# CONNECTORs.net
KiCad netlist of a schematic drawn in Altium Designer
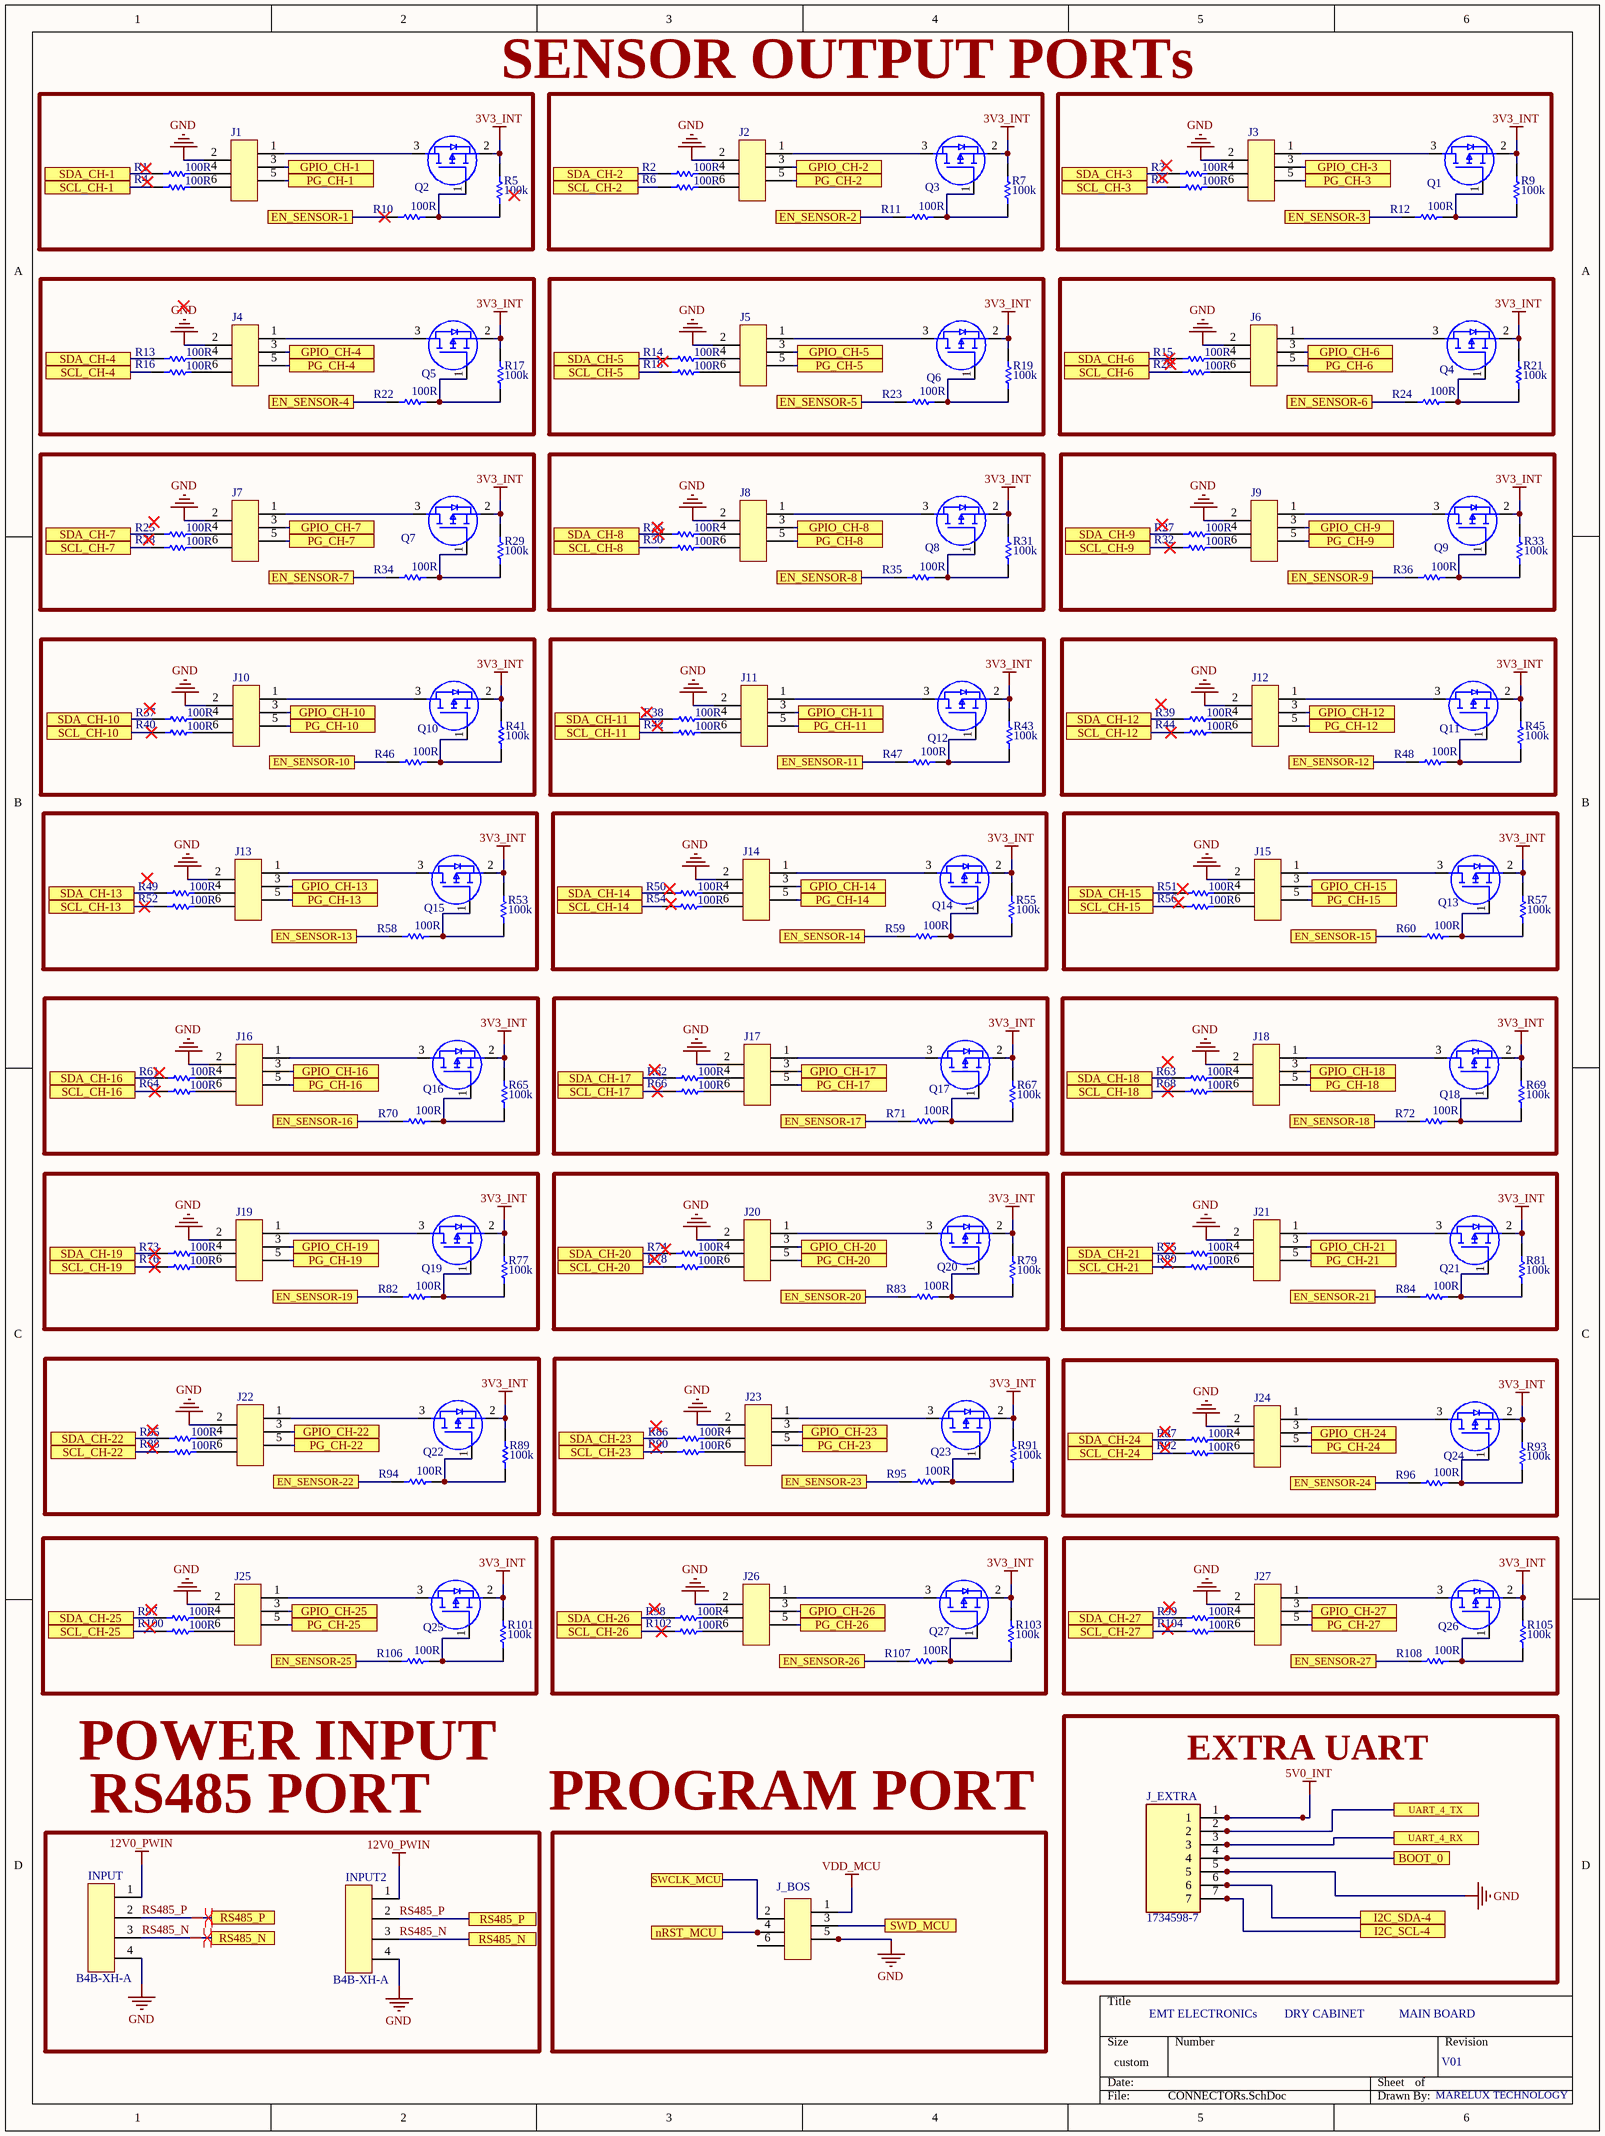
[diagram p0: CONNECTORs.SchDoc]

(export (version "E")
  (design (tool "Eeschema 10.0.6"))
  (components
    (comp (ref "INPUT")
      (value "B4B-XH-A")
      (footprint "B4B-XH-A")
      (description "CONN HEADER VERT 4POS 2.5MM")
      (fields (field (name "MANUFACTURER") "JST"))
      (libsource (lib "MareLux24Lib") (part "B4B-XH-A"))
    )
    (comp (ref "INPUT2")
      (value "B4B-XH-A")
      (footprint "B4B-XH-A")
      (description "CONN HEADER VERT 4POS 2.5MM")
      (fields (field (name "MANUFACTURER") "JST"))
      (libsource (lib "MareLux24Lib") (part "B4B-XH-A"))
    )
    (comp (ref "J1")
      (value "009159006651906")
      (footprint "009159006651906")
      (description "CONN EDGE DUAL FMALE 6POS 0.024")
      (fields (field (name "MANUFACTURER") "KYOCERA AVX"))
      (libsource (lib "MareLux24Lib") (part "009159006651906"))
    )
    (comp (ref "J2")
      (value "009159006651906")
      (footprint "009159006651906")
      (description "CONN EDGE DUAL FMALE 6POS 0.024")
      (fields (field (name "MANUFACTURER") "KYOCERA AVX"))
      (libsource (lib "MareLux24Lib") (part "009159006651906"))
    )
    (comp (ref "J3")
      (value "009159006651906")
      (footprint "009159006651906")
      (description "CONN EDGE DUAL FMALE 6POS 0.024")
      (fields (field (name "MANUFACTURER") "KYOCERA AVX"))
      (libsource (lib "MareLux24Lib") (part "009159006651906"))
    )
    (comp (ref "J4")
      (value "009159006651906")
      (footprint "009159006651906")
      (description "CONN EDGE DUAL FMALE 6POS 0.024")
      (fields (field (name "MANUFACTURER") "KYOCERA AVX"))
      (libsource (lib "MareLux24Lib") (part "009159006651906"))
    )
    (comp (ref "J5")
      (value "009159006651906")
      (footprint "009159006651906")
      (description "CONN EDGE DUAL FMALE 6POS 0.024")
      (fields (field (name "MANUFACTURER") "KYOCERA AVX"))
      (libsource (lib "MareLux24Lib") (part "009159006651906"))
    )
    (comp (ref "J6")
      (value "009159006651906")
      (footprint "009159006651906")
      (description "CONN EDGE DUAL FMALE 6POS 0.024")
      (fields (field (name "MANUFACTURER") "KYOCERA AVX"))
      (libsource (lib "MareLux24Lib") (part "009159006651906"))
    )
    (comp (ref "J7")
      (value "009159006651906")
      (footprint "009159006651906")
      (description "CONN EDGE DUAL FMALE 6POS 0.024")
      (fields (field (name "MANUFACTURER") "KYOCERA AVX"))
      (libsource (lib "MareLux24Lib") (part "009159006651906"))
    )
    (comp (ref "J8")
      (value "009159006651906")
      (footprint "009159006651906")
      (description "CONN EDGE DUAL FMALE 6POS 0.024")
      (fields (field (name "MANUFACTURER") "KYOCERA AVX"))
      (libsource (lib "MareLux24Lib") (part "009159006651906"))
    )
    (comp (ref "J9")
      (value "009159006651906")
      (footprint "009159006651906")
      (description "CONN EDGE DUAL FMALE 6POS 0.024")
      (fields (field (name "MANUFACTURER") "KYOCERA AVX"))
      (libsource (lib "MareLux24Lib") (part "009159006651906"))
    )
    (comp (ref "J10")
      (value "009159006651906")
      (footprint "009159006651906")
      (description "CONN EDGE DUAL FMALE 6POS 0.024")
      (fields (field (name "MANUFACTURER") "KYOCERA AVX"))
      (libsource (lib "MareLux24Lib") (part "009159006651906"))
    )
    (comp (ref "J11")
      (value "009159006651906")
      (footprint "009159006651906")
      (description "CONN EDGE DUAL FMALE 6POS 0.024")
      (fields (field (name "MANUFACTURER") "KYOCERA AVX"))
      (libsource (lib "MareLux24Lib") (part "009159006651906"))
    )
    (comp (ref "J12")
      (value "009159006651906")
      (footprint "009159006651906")
      (description "CONN EDGE DUAL FMALE 6POS 0.024")
      (fields (field (name "MANUFACTURER") "KYOCERA AVX"))
      (libsource (lib "MareLux24Lib") (part "009159006651906"))
    )
    (comp (ref "J13")
      (value "009159006651906")
      (footprint "009159006651906")
      (description "CONN EDGE DUAL FMALE 6POS 0.024")
      (fields (field (name "MANUFACTURER") "KYOCERA AVX"))
      (libsource (lib "MareLux24Lib") (part "009159006651906"))
    )
    (comp (ref "J14")
      (value "009159006651906")
      (footprint "009159006651906")
      (description "CONN EDGE DUAL FMALE 6POS 0.024")
      (fields (field (name "MANUFACTURER") "KYOCERA AVX"))
      (libsource (lib "MareLux24Lib") (part "009159006651906"))
    )
    (comp (ref "J15")
      (value "009159006651906")
      (footprint "009159006651906")
      (description "CONN EDGE DUAL FMALE 6POS 0.024")
      (fields (field (name "MANUFACTURER") "KYOCERA AVX"))
      (libsource (lib "MareLux24Lib") (part "009159006651906"))
    )
    (comp (ref "J16")
      (value "009159006651906")
      (footprint "009159006651906")
      (description "CONN EDGE DUAL FMALE 6POS 0.024")
      (fields (field (name "MANUFACTURER") "KYOCERA AVX"))
      (libsource (lib "MareLux24Lib") (part "009159006651906"))
    )
    (comp (ref "J17")
      (value "009159006651906")
      (footprint "009159006651906")
      (description "CONN EDGE DUAL FMALE 6POS 0.024")
      (fields (field (name "MANUFACTURER") "KYOCERA AVX"))
      (libsource (lib "MareLux24Lib") (part "009159006651906"))
    )
    (comp (ref "J18")
      (value "009159006651906")
      (footprint "009159006651906")
      (description "CONN EDGE DUAL FMALE 6POS 0.024")
      (fields (field (name "MANUFACTURER") "KYOCERA AVX"))
      (libsource (lib "MareLux24Lib") (part "009159006651906"))
    )
    (comp (ref "J19")
      (value "009159006651906")
      (footprint "009159006651906")
      (description "CONN EDGE DUAL FMALE 6POS 0.024")
      (fields (field (name "MANUFACTURER") "KYOCERA AVX"))
      (libsource (lib "MareLux24Lib") (part "009159006651906"))
    )
    (comp (ref "J20")
      (value "009159006651906")
      (footprint "009159006651906")
      (description "CONN EDGE DUAL FMALE 6POS 0.024")
      (fields (field (name "MANUFACTURER") "KYOCERA AVX"))
      (libsource (lib "MareLux24Lib") (part "009159006651906"))
    )
    (comp (ref "J21")
      (value "009159006651906")
      (footprint "009159006651906")
      (description "CONN EDGE DUAL FMALE 6POS 0.024")
      (fields (field (name "MANUFACTURER") "KYOCERA AVX"))
      (libsource (lib "MareLux24Lib") (part "009159006651906"))
    )
    (comp (ref "J22")
      (value "009159006651906")
      (footprint "009159006651906")
      (description "CONN EDGE DUAL FMALE 6POS 0.024")
      (fields (field (name "MANUFACTURER") "KYOCERA AVX"))
      (libsource (lib "MareLux24Lib") (part "009159006651906"))
    )
    (comp (ref "J23")
      (value "009159006651906")
      (footprint "009159006651906")
      (description "CONN EDGE DUAL FMALE 6POS 0.024")
      (fields (field (name "MANUFACTURER") "KYOCERA AVX"))
      (libsource (lib "MareLux24Lib") (part "009159006651906"))
    )
    (comp (ref "J24")
      (value "009159006651906")
      (footprint "009159006651906")
      (description "CONN EDGE DUAL FMALE 6POS 0.024")
      (fields (field (name "MANUFACTURER") "KYOCERA AVX"))
      (libsource (lib "MareLux24Lib") (part "009159006651906"))
    )
    (comp (ref "J25")
      (value "009159006651906")
      (footprint "009159006651906")
      (description "CONN EDGE DUAL FMALE 6POS 0.024")
      (fields (field (name "MANUFACTURER") "KYOCERA AVX"))
      (libsource (lib "MareLux24Lib") (part "009159006651906"))
    )
    (comp (ref "J26")
      (value "009159006651906")
      (footprint "009159006651906")
      (description "CONN EDGE DUAL FMALE 6POS 0.024")
      (fields (field (name "MANUFACTURER") "KYOCERA AVX"))
      (libsource (lib "MareLux24Lib") (part "009159006651906"))
    )
    (comp (ref "J27")
      (value "009159006651906")
      (footprint "009159006651906")
      (description "CONN EDGE DUAL FMALE 6POS 0.024")
      (fields (field (name "MANUFACTURER") "KYOCERA AVX"))
      (libsource (lib "MareLux24Lib") (part "009159006651906"))
    )
    (comp (ref "J_BOS")
      (value "009159006651906")
      (footprint "009159006651906")
      (description "CONN EDGE DUAL FMALE 6POS 0.024")
      (fields (field (name "MANUFACTURER") "KYOCERA AVX"))
      (libsource (lib "MareLux24Lib") (part "009159006651906"))
    )
    (comp (ref "J_EXTRA")
      (value "1734598-7")
      (footprint "TE_1734598-7")
      (description "Connector Header Through Hole 7 position 0.049 (1.25mm)")
      (fields (field (name "DIGI-KEY_PART_NUMBER") "A99919-ND") (field (name "MF") "TE Connectivity"))
      (libsource (lib "1734598-7") (part "1734598-7"))
    )
    (comp (ref "Q1")
      (value "GSF3407")
      (footprint "SOT-23")
      (description "P-Channel 30 V 4.1A (Ta) 1.2W (Ta) Surface Mount SOT-23")
      (fields (field (name "VOLTAGE") "30 V") (field (name "POWER") "1200 mW"))
      (libsource (lib "MareLux24Lib") (part "GSF3407"))
    )
    (comp (ref "Q2")
      (value "GSF3407")
      (footprint "SOT-23")
      (description "P-Channel 30 V 4.1A (Ta) 1.2W (Ta) Surface Mount SOT-23")
      (fields (field (name "VOLTAGE") "30 V") (field (name "POWER") "1200 mW"))
      (libsource (lib "MareLux24Lib") (part "GSF3407"))
    )
    (comp (ref "Q3")
      (value "GSF3407")
      (footprint "SOT-23")
      (description "P-Channel 30 V 4.1A (Ta) 1.2W (Ta) Surface Mount SOT-23")
      (fields (field (name "VOLTAGE") "30 V") (field (name "POWER") "1200 mW"))
      (libsource (lib "MareLux24Lib") (part "GSF3407"))
    )
    (comp (ref "Q4")
      (value "GSF3407")
      (footprint "SOT-23")
      (description "P-Channel 30 V 4.1A (Ta) 1.2W (Ta) Surface Mount SOT-23")
      (fields (field (name "VOLTAGE") "30 V") (field (name "POWER") "1200 mW"))
      (libsource (lib "MareLux24Lib") (part "GSF3407"))
    )
    (comp (ref "Q5")
      (value "GSF3407")
      (footprint "SOT-23")
      (description "P-Channel 30 V 4.1A (Ta) 1.2W (Ta) Surface Mount SOT-23")
      (fields (field (name "VOLTAGE") "30 V") (field (name "POWER") "1200 mW"))
      (libsource (lib "MareLux24Lib") (part "GSF3407"))
    )
    (comp (ref "Q6")
      (value "GSF3407")
      (footprint "SOT-23")
      (description "P-Channel 30 V 4.1A (Ta) 1.2W (Ta) Surface Mount SOT-23")
      (fields (field (name "VOLTAGE") "30 V") (field (name "POWER") "1200 mW"))
      (libsource (lib "MareLux24Lib") (part "GSF3407"))
    )
    (comp (ref "Q7")
      (value "GSF3407")
      (footprint "SOT-23")
      (description "P-Channel 30 V 4.1A (Ta) 1.2W (Ta) Surface Mount SOT-23")
      (fields (field (name "VOLTAGE") "30 V") (field (name "POWER") "1200 mW"))
      (libsource (lib "MareLux24Lib") (part "GSF3407"))
    )
    (comp (ref "Q8")
      (value "GSF3407")
      (footprint "SOT-23")
      (description "P-Channel 30 V 4.1A (Ta) 1.2W (Ta) Surface Mount SOT-23")
      (fields (field (name "VOLTAGE") "30 V") (field (name "POWER") "1200 mW"))
      (libsource (lib "MareLux24Lib") (part "GSF3407"))
    )
    (comp (ref "Q9")
      (value "GSF3407")
      (footprint "SOT-23")
      (description "P-Channel 30 V 4.1A (Ta) 1.2W (Ta) Surface Mount SOT-23")
      (fields (field (name "VOLTAGE") "30 V") (field (name "POWER") "1200 mW"))
      (libsource (lib "MareLux24Lib") (part "GSF3407"))
    )
    (comp (ref "Q10")
      (value "GSF3407")
      (footprint "SOT-23")
      (description "P-Channel 30 V 4.1A (Ta) 1.2W (Ta) Surface Mount SOT-23")
      (fields (field (name "VOLTAGE") "30 V") (field (name "POWER") "1200 mW"))
      (libsource (lib "MareLux24Lib") (part "GSF3407"))
    )
    (comp (ref "Q11")
      (value "GSF3407")
      (footprint "SOT-23")
      (description "P-Channel 30 V 4.1A (Ta) 1.2W (Ta) Surface Mount SOT-23")
      (fields (field (name "VOLTAGE") "30 V") (field (name "POWER") "1200 mW"))
      (libsource (lib "MareLux24Lib") (part "GSF3407"))
    )
    (comp (ref "Q12")
      (value "GSF3407")
      (footprint "SOT-23")
      (description "P-Channel 30 V 4.1A (Ta) 1.2W (Ta) Surface Mount SOT-23")
      (fields (field (name "VOLTAGE") "30 V") (field (name "POWER") "1200 mW"))
      (libsource (lib "MareLux24Lib") (part "GSF3407"))
    )
    (comp (ref "Q13")
      (value "GSF3407")
      (footprint "SOT-23")
      (description "P-Channel 30 V 4.1A (Ta) 1.2W (Ta) Surface Mount SOT-23")
      (fields (field (name "VOLTAGE") "30 V") (field (name "POWER") "1200 mW"))
      (libsource (lib "MareLux24Lib") (part "GSF3407"))
    )
    (comp (ref "Q14")
      (value "GSF3407")
      (footprint "SOT-23")
      (description "P-Channel 30 V 4.1A (Ta) 1.2W (Ta) Surface Mount SOT-23")
      (fields (field (name "VOLTAGE") "30 V") (field (name "POWER") "1200 mW"))
      (libsource (lib "MareLux24Lib") (part "GSF3407"))
    )
    (comp (ref "Q15")
      (value "GSF3407")
      (footprint "SOT-23")
      (description "P-Channel 30 V 4.1A (Ta) 1.2W (Ta) Surface Mount SOT-23")
      (fields (field (name "VOLTAGE") "30 V") (field (name "POWER") "1200 mW"))
      (libsource (lib "MareLux24Lib") (part "GSF3407"))
    )
    (comp (ref "Q16")
      (value "GSF3407")
      (footprint "SOT-23")
      (description "P-Channel 30 V 4.1A (Ta) 1.2W (Ta) Surface Mount SOT-23")
      (fields (field (name "VOLTAGE") "30 V") (field (name "POWER") "1200 mW"))
      (libsource (lib "MareLux24Lib") (part "GSF3407"))
    )
    (comp (ref "Q17")
      (value "GSF3407")
      (footprint "SOT-23")
      (description "P-Channel 30 V 4.1A (Ta) 1.2W (Ta) Surface Mount SOT-23")
      (fields (field (name "VOLTAGE") "30 V") (field (name "POWER") "1200 mW"))
      (libsource (lib "MareLux24Lib") (part "GSF3407"))
    )
    (comp (ref "Q18")
      (value "GSF3407")
      (footprint "SOT-23")
      (description "P-Channel 30 V 4.1A (Ta) 1.2W (Ta) Surface Mount SOT-23")
      (fields (field (name "VOLTAGE") "30 V") (field (name "POWER") "1200 mW"))
      (libsource (lib "MareLux24Lib") (part "GSF3407"))
    )
    (comp (ref "Q19")
      (value "GSF3407")
      (footprint "SOT-23")
      (description "P-Channel 30 V 4.1A (Ta) 1.2W (Ta) Surface Mount SOT-23")
      (fields (field (name "VOLTAGE") "30 V") (field (name "POWER") "1200 mW"))
      (libsource (lib "MareLux24Lib") (part "GSF3407"))
    )
    (comp (ref "Q20")
      (value "GSF3407")
      (footprint "SOT-23")
      (description "P-Channel 30 V 4.1A (Ta) 1.2W (Ta) Surface Mount SOT-23")
      (fields (field (name "VOLTAGE") "30 V") (field (name "POWER") "1200 mW"))
      (libsource (lib "MareLux24Lib") (part "GSF3407"))
    )
    (comp (ref "Q21")
      (value "GSF3407")
      (footprint "SOT-23")
      (description "P-Channel 30 V 4.1A (Ta) 1.2W (Ta) Surface Mount SOT-23")
      (fields (field (name "VOLTAGE") "30 V") (field (name "POWER") "1200 mW"))
      (libsource (lib "MareLux24Lib") (part "GSF3407"))
    )
    (comp (ref "Q22")
      (value "GSF3407")
      (footprint "SOT-23")
      (description "P-Channel 30 V 4.1A (Ta) 1.2W (Ta) Surface Mount SOT-23")
      (fields (field (name "VOLTAGE") "30 V") (field (name "POWER") "1200 mW"))
      (libsource (lib "MareLux24Lib") (part "GSF3407"))
    )
    (comp (ref "Q23")
      (value "GSF3407")
      (footprint "SOT-23")
      (description "P-Channel 30 V 4.1A (Ta) 1.2W (Ta) Surface Mount SOT-23")
      (fields (field (name "VOLTAGE") "30 V") (field (name "POWER") "1200 mW"))
      (libsource (lib "MareLux24Lib") (part "GSF3407"))
    )
    (comp (ref "Q24")
      (value "GSF3407")
      (footprint "SOT-23")
      (description "P-Channel 30 V 4.1A (Ta) 1.2W (Ta) Surface Mount SOT-23")
      (fields (field (name "VOLTAGE") "30 V") (field (name "POWER") "1200 mW"))
      (libsource (lib "MareLux24Lib") (part "GSF3407"))
    )
    (comp (ref "Q25")
      (value "GSF3407")
      (footprint "SOT-23")
      (description "P-Channel 30 V 4.1A (Ta) 1.2W (Ta) Surface Mount SOT-23")
      (fields (field (name "VOLTAGE") "30 V") (field (name "POWER") "1200 mW"))
      (libsource (lib "MareLux24Lib") (part "GSF3407"))
    )
    (comp (ref "Q26")
      (value "GSF3407")
      (footprint "SOT-23")
      (description "P-Channel 30 V 4.1A (Ta) 1.2W (Ta) Surface Mount SOT-23")
      (fields (field (name "VOLTAGE") "30 V") (field (name "POWER") "1200 mW"))
      (libsource (lib "MareLux24Lib") (part "GSF3407"))
    )
    (comp (ref "Q27")
      (value "GSF3407")
      (footprint "SOT-23")
      (description "P-Channel 30 V 4.1A (Ta) 1.2W (Ta) Surface Mount SOT-23")
      (fields (field (name "VOLTAGE") "30 V") (field (name "POWER") "1200 mW"))
      (libsource (lib "MareLux24Lib") (part "GSF3407"))
    )
    (comp (ref "R1")
      (value "100R")
      (footprint "MareLux24Lib:RES_0402_SMD")
      (description "Generic Chip Res 100R")
      (fields (field (name "PART NUMBER") "RMCF0402JT100R") (field (name "TOLERANCE") "5 %"))
      (libsource (lib "MareLux24Lib") (part "RES_GEN_SMD"))
    )
    (comp (ref "R2")
      (value "100R")
      (footprint "MareLux24Lib:RES_0402_SMD")
      (description "Generic Chip Res 100R")
      (fields (field (name "PART NUMBER") "RMCF0402JT100R") (field (name "TOLERANCE") "5 %"))
      (libsource (lib "MareLux24Lib") (part "RES_GEN_SMD"))
    )
    (comp (ref "R3")
      (value "100R")
      (footprint "MareLux24Lib:RES_0402_SMD")
      (description "Generic Chip Res 100R")
      (fields (field (name "PART NUMBER") "RMCF0402JT100R") (field (name "TOLERANCE") "5 %"))
      (libsource (lib "MareLux24Lib") (part "RES_GEN_SMD"))
    )
    (comp (ref "R4")
      (value "100R")
      (footprint "MareLux24Lib:RES_0402_SMD")
      (description "Generic Chip Res 100R")
      (fields (field (name "PART NUMBER") "RMCF0402JT100R") (field (name "TOLERANCE") "5 %"))
      (libsource (lib "MareLux24Lib") (part "RES_GEN_SMD"))
    )
    (comp (ref "R5")
      (value "100k")
      (footprint "MareLux24Lib:RES_0402_SMD")
      (description "Generic Chip Res 158k")
      (fields (field (name "PART NUMBER") "RMCF0402JT100K") (field (name "TOLERANCE") "5%"))
      (libsource (lib "MareLux24Lib") (part "RES_GEN_SMD"))
    )
    (comp (ref "R6")
      (value "100R")
      (footprint "MareLux24Lib:RES_0402_SMD")
      (description "Generic Chip Res 100R")
      (fields (field (name "PART NUMBER") "RMCF0402JT100R") (field (name "TOLERANCE") "5 %"))
      (libsource (lib "MareLux24Lib") (part "RES_GEN_SMD"))
    )
    (comp (ref "R7")
      (value "100k")
      (footprint "MareLux24Lib:RES_0402_SMD")
      (description "Generic Chip Res 158k")
      (fields (field (name "PART NUMBER") "RMCF0402JT100K") (field (name "TOLERANCE") "5%"))
      (libsource (lib "MareLux24Lib") (part "RES_GEN_SMD"))
    )
    (comp (ref "R8")
      (value "100R")
      (footprint "MareLux24Lib:RES_0402_SMD")
      (description "Generic Chip Res 100R")
      (fields (field (name "PART NUMBER") "RMCF0402JT100R") (field (name "TOLERANCE") "5 %"))
      (libsource (lib "MareLux24Lib") (part "RES_GEN_SMD"))
    )
    (comp (ref "R9")
      (value "100k")
      (footprint "MareLux24Lib:RES_0402_SMD")
      (description "Generic Chip Res 158k")
      (fields (field (name "PART NUMBER") "RMCF0402JT100K") (field (name "TOLERANCE") "5%"))
      (libsource (lib "MareLux24Lib") (part "RES_GEN_SMD"))
    )
    (comp (ref "R10")
      (value "100R")
      (footprint "MareLux24Lib:RES_0402_SMD")
      (description "Generic Chip Res 100R")
      (fields (field (name "PART NUMBER") "RMCF0402JT100R") (field (name "TOLERANCE") "5 %"))
      (libsource (lib "MareLux24Lib") (part "RES_GEN_SMD"))
    )
    (comp (ref "R11")
      (value "100R")
      (footprint "MareLux24Lib:RES_0402_SMD")
      (description "Generic Chip Res 100R")
      (fields (field (name "PART NUMBER") "RMCF0402JT100R") (field (name "TOLERANCE") "5 %"))
      (libsource (lib "MareLux24Lib") (part "RES_GEN_SMD"))
    )
    (comp (ref "R12")
      (value "100R")
      (footprint "MareLux24Lib:RES_0402_SMD")
      (description "Generic Chip Res 100R")
      (fields (field (name "PART NUMBER") "RMCF0402JT100R") (field (name "TOLERANCE") "5 %"))
      (libsource (lib "MareLux24Lib") (part "RES_GEN_SMD"))
    )
    (comp (ref "R13")
      (value "100R")
      (footprint "MareLux24Lib:RES_0402_SMD")
      (description "Generic Chip Res 100R")
      (fields (field (name "PART NUMBER") "RMCF0402JT100R") (field (name "TOLERANCE") "5 %"))
      (libsource (lib "MareLux24Lib") (part "RES_GEN_SMD"))
    )
    (comp (ref "R14")
      (value "100R")
      (footprint "MareLux24Lib:RES_0402_SMD")
      (description "Generic Chip Res 100R")
      (fields (field (name "PART NUMBER") "RMCF0402JT100R") (field (name "TOLERANCE") "5 %"))
      (libsource (lib "MareLux24Lib") (part "RES_GEN_SMD"))
    )
    (comp (ref "R15")
      (value "100R")
      (footprint "MareLux24Lib:RES_0402_SMD")
      (description "Generic Chip Res 100R")
      (fields (field (name "PART NUMBER") "RMCF0402JT100R") (field (name "TOLERANCE") "5 %"))
      (libsource (lib "MareLux24Lib") (part "RES_GEN_SMD"))
    )
    (comp (ref "R16")
      (value "100R")
      (footprint "MareLux24Lib:RES_0402_SMD")
      (description "Generic Chip Res 100R")
      (fields (field (name "PART NUMBER") "RMCF0402JT100R") (field (name "TOLERANCE") "5 %"))
      (libsource (lib "MareLux24Lib") (part "RES_GEN_SMD"))
    )
    (comp (ref "R17")
      (value "100k")
      (footprint "MareLux24Lib:RES_0402_SMD")
      (description "Generic Chip Res 158k")
      (fields (field (name "PART NUMBER") "RMCF0402JT100K") (field (name "TOLERANCE") "5%"))
      (libsource (lib "MareLux24Lib") (part "RES_GEN_SMD"))
    )
    (comp (ref "R18")
      (value "100R")
      (footprint "MareLux24Lib:RES_0402_SMD")
      (description "Generic Chip Res 100R")
      (fields (field (name "PART NUMBER") "RMCF0402JT100R") (field (name "TOLERANCE") "5 %"))
      (libsource (lib "MareLux24Lib") (part "RES_GEN_SMD"))
    )
    (comp (ref "R19")
      (value "100k")
      (footprint "MareLux24Lib:RES_0402_SMD")
      (description "Generic Chip Res 158k")
      (fields (field (name "PART NUMBER") "RMCF0402JT100K") (field (name "TOLERANCE") "5%"))
      (libsource (lib "MareLux24Lib") (part "RES_GEN_SMD"))
    )
    (comp (ref "R20")
      (value "100R")
      (footprint "MareLux24Lib:RES_0402_SMD")
      (description "Generic Chip Res 100R")
      (fields (field (name "PART NUMBER") "RMCF0402JT100R") (field (name "TOLERANCE") "5 %"))
      (libsource (lib "MareLux24Lib") (part "RES_GEN_SMD"))
    )
    (comp (ref "R21")
      (value "100k")
      (footprint "MareLux24Lib:RES_0402_SMD")
      (description "Generic Chip Res 158k")
      (fields (field (name "PART NUMBER") "RMCF0402JT100K") (field (name "TOLERANCE") "5%"))
      (libsource (lib "MareLux24Lib") (part "RES_GEN_SMD"))
    )
    (comp (ref "R22")
      (value "100R")
      (footprint "MareLux24Lib:RES_0402_SMD")
      (description "Generic Chip Res 100R")
      (fields (field (name "PART NUMBER") "RMCF0402JT100R") (field (name "TOLERANCE") "5 %"))
      (libsource (lib "MareLux24Lib") (part "RES_GEN_SMD"))
    )
    (comp (ref "R23")
      (value "100R")
      (footprint "MareLux24Lib:RES_0402_SMD")
      (description "Generic Chip Res 100R")
      (fields (field (name "PART NUMBER") "RMCF0402JT100R") (field (name "TOLERANCE") "5 %"))
      (libsource (lib "MareLux24Lib") (part "RES_GEN_SMD"))
    )
    (comp (ref "R24")
      (value "100R")
      (footprint "MareLux24Lib:RES_0402_SMD")
      (description "Generic Chip Res 100R")
      (fields (field (name "PART NUMBER") "RMCF0402JT100R") (field (name "TOLERANCE") "5 %"))
      (libsource (lib "MareLux24Lib") (part "RES_GEN_SMD"))
    )
    (comp (ref "R25")
      (value "100R")
      (footprint "MareLux24Lib:RES_0402_SMD")
      (description "Generic Chip Res 100R")
      (fields (field (name "PART NUMBER") "RMCF0402JT100R") (field (name "TOLERANCE") "5 %"))
      (libsource (lib "MareLux24Lib") (part "RES_GEN_SMD"))
    )
    (comp (ref "R26")
      (value "100R")
      (footprint "MareLux24Lib:RES_0402_SMD")
      (description "Generic Chip Res 100R")
      (fields (field (name "PART NUMBER") "RMCF0402JT100R") (field (name "TOLERANCE") "5 %"))
      (libsource (lib "MareLux24Lib") (part "RES_GEN_SMD"))
    )
    (comp (ref "R27")
      (value "100R")
      (footprint "MareLux24Lib:RES_0402_SMD")
      (description "Generic Chip Res 100R")
      (fields (field (name "PART NUMBER") "RMCF0402JT100R") (field (name "TOLERANCE") "5 %"))
      (libsource (lib "MareLux24Lib") (part "RES_GEN_SMD"))
    )
    (comp (ref "R28")
      (value "100R")
      (footprint "MareLux24Lib:RES_0402_SMD")
      (description "Generic Chip Res 100R")
      (fields (field (name "PART NUMBER") "RMCF0402JT100R") (field (name "TOLERANCE") "5 %"))
      (libsource (lib "MareLux24Lib") (part "RES_GEN_SMD"))
    )
    (comp (ref "R29")
      (value "100k")
      (footprint "MareLux24Lib:RES_0402_SMD")
      (description "Generic Chip Res 158k")
      (fields (field (name "PART NUMBER") "RMCF0402JT100K") (field (name "TOLERANCE") "5%"))
      (libsource (lib "MareLux24Lib") (part "RES_GEN_SMD"))
    )
    (comp (ref "R30")
      (value "100R")
      (footprint "MareLux24Lib:RES_0402_SMD")
      (description "Generic Chip Res 100R")
      (fields (field (name "PART NUMBER") "RMCF0402JT100R") (field (name "TOLERANCE") "5 %"))
      (libsource (lib "MareLux24Lib") (part "RES_GEN_SMD"))
    )
    (comp (ref "R31")
      (value "100k")
      (footprint "MareLux24Lib:RES_0402_SMD")
      (description "Generic Chip Res 158k")
      (fields (field (name "PART NUMBER") "RMCF0402JT100K") (field (name "TOLERANCE") "5%"))
      (libsource (lib "MareLux24Lib") (part "RES_GEN_SMD"))
    )
    (comp (ref "R32")
      (value "100R")
      (footprint "MareLux24Lib:RES_0402_SMD")
      (description "Generic Chip Res 100R")
      (fields (field (name "PART NUMBER") "RMCF0402JT100R") (field (name "TOLERANCE") "5 %"))
      (libsource (lib "MareLux24Lib") (part "RES_GEN_SMD"))
    )
    (comp (ref "R33")
      (value "100k")
      (footprint "MareLux24Lib:RES_0402_SMD")
      (description "Generic Chip Res 158k")
      (fields (field (name "PART NUMBER") "RMCF0402JT100K") (field (name "TOLERANCE") "5%"))
      (libsource (lib "MareLux24Lib") (part "RES_GEN_SMD"))
    )
    (comp (ref "R34")
      (value "100R")
      (footprint "MareLux24Lib:RES_0402_SMD")
      (description "Generic Chip Res 100R")
      (fields (field (name "PART NUMBER") "RMCF0402JT100R") (field (name "TOLERANCE") "5 %"))
      (libsource (lib "MareLux24Lib") (part "RES_GEN_SMD"))
    )
    (comp (ref "R35")
      (value "100R")
      (footprint "MareLux24Lib:RES_0402_SMD")
      (description "Generic Chip Res 100R")
      (fields (field (name "PART NUMBER") "RMCF0402JT100R") (field (name "TOLERANCE") "5 %"))
      (libsource (lib "MareLux24Lib") (part "RES_GEN_SMD"))
    )
    (comp (ref "R36")
      (value "100R")
      (footprint "MareLux24Lib:RES_0402_SMD")
      (description "Generic Chip Res 100R")
      (fields (field (name "PART NUMBER") "RMCF0402JT100R") (field (name "TOLERANCE") "5 %"))
      (libsource (lib "MareLux24Lib") (part "RES_GEN_SMD"))
    )
    (comp (ref "R37")
      (value "100R")
      (footprint "MareLux24Lib:RES_0402_SMD")
      (description "Generic Chip Res 100R")
      (fields (field (name "PART NUMBER") "RMCF0402JT100R") (field (name "TOLERANCE") "5 %"))
      (libsource (lib "MareLux24Lib") (part "RES_GEN_SMD"))
    )
    (comp (ref "R38")
      (value "100R")
      (footprint "MareLux24Lib:RES_0402_SMD")
      (description "Generic Chip Res 100R")
      (fields (field (name "PART NUMBER") "RMCF0402JT100R") (field (name "TOLERANCE") "5 %"))
      (libsource (lib "MareLux24Lib") (part "RES_GEN_SMD"))
    )
    (comp (ref "R39")
      (value "100R")
      (footprint "MareLux24Lib:RES_0402_SMD")
      (description "Generic Chip Res 100R")
      (fields (field (name "PART NUMBER") "RMCF0402JT100R") (field (name "TOLERANCE") "5 %"))
      (libsource (lib "MareLux24Lib") (part "RES_GEN_SMD"))
    )
    (comp (ref "R40")
      (value "100R")
      (footprint "MareLux24Lib:RES_0402_SMD")
      (description "Generic Chip Res 100R")
      (fields (field (name "PART NUMBER") "RMCF0402JT100R") (field (name "TOLERANCE") "5 %"))
      (libsource (lib "MareLux24Lib") (part "RES_GEN_SMD"))
    )
    (comp (ref "R41")
      (value "100k")
      (footprint "MareLux24Lib:RES_0402_SMD")
      (description "Generic Chip Res 158k")
      (fields (field (name "PART NUMBER") "RMCF0402JT100K") (field (name "TOLERANCE") "5%"))
      (libsource (lib "MareLux24Lib") (part "RES_GEN_SMD"))
    )
    (comp (ref "R42")
      (value "100R")
      (footprint "MareLux24Lib:RES_0402_SMD")
      (description "Generic Chip Res 100R")
      (fields (field (name "PART NUMBER") "RMCF0402JT100R") (field (name "TOLERANCE") "5 %"))
      (libsource (lib "MareLux24Lib") (part "RES_GEN_SMD"))
    )
    (comp (ref "R43")
      (value "100k")
      (footprint "MareLux24Lib:RES_0402_SMD")
      (description "Generic Chip Res 158k")
      (fields (field (name "PART NUMBER") "RMCF0402JT100K") (field (name "TOLERANCE") "5%"))
      (libsource (lib "MareLux24Lib") (part "RES_GEN_SMD"))
    )
    (comp (ref "R44")
      (value "100R")
      (footprint "MareLux24Lib:RES_0402_SMD")
      (description "Generic Chip Res 100R")
      (fields (field (name "PART NUMBER") "RMCF0402JT100R") (field (name "TOLERANCE") "5 %"))
      (libsource (lib "MareLux24Lib") (part "RES_GEN_SMD"))
    )
    (comp (ref "R45")
      (value "100k")
      (footprint "MareLux24Lib:RES_0402_SMD")
      (description "Generic Chip Res 158k")
      (fields (field (name "PART NUMBER") "RMCF0402JT100K") (field (name "TOLERANCE") "5%"))
      (libsource (lib "MareLux24Lib") (part "RES_GEN_SMD"))
    )
    (comp (ref "R46")
      (value "100R")
      (footprint "MareLux24Lib:RES_0402_SMD")
      (description "Generic Chip Res 100R")
      (fields (field (name "PART NUMBER") "RMCF0402JT100R") (field (name "TOLERANCE") "5 %"))
      (libsource (lib "MareLux24Lib") (part "RES_GEN_SMD"))
    )
    (comp (ref "R47")
      (value "100R")
      (footprint "MareLux24Lib:RES_0402_SMD")
      (description "Generic Chip Res 100R")
      (fields (field (name "PART NUMBER") "RMCF0402JT100R") (field (name "TOLERANCE") "5 %"))
      (libsource (lib "MareLux24Lib") (part "RES_GEN_SMD"))
    )
    (comp (ref "R48")
      (value "100R")
      (footprint "MareLux24Lib:RES_0402_SMD")
      (description "Generic Chip Res 100R")
      (fields (field (name "PART NUMBER") "RMCF0402JT100R") (field (name "TOLERANCE") "5 %"))
      (libsource (lib "MareLux24Lib") (part "RES_GEN_SMD"))
    )
    (comp (ref "R49")
      (value "100R")
      (footprint "MareLux24Lib:RES_0402_SMD")
      (description "Generic Chip Res 100R")
      (fields (field (name "PART NUMBER") "RMCF0402JT100R") (field (name "TOLERANCE") "5 %"))
      (libsource (lib "MareLux24Lib") (part "RES_GEN_SMD"))
    )
    (comp (ref "R50")
      (value "100R")
      (footprint "MareLux24Lib:RES_0402_SMD")
      (description "Generic Chip Res 100R")
      (fields (field (name "PART NUMBER") "RMCF0402JT100R") (field (name "TOLERANCE") "5 %"))
      (libsource (lib "MareLux24Lib") (part "RES_GEN_SMD"))
    )
    (comp (ref "R51")
      (value "100R")
      (footprint "MareLux24Lib:RES_0402_SMD")
      (description "Generic Chip Res 100R")
      (fields (field (name "PART NUMBER") "RMCF0402JT100R") (field (name "TOLERANCE") "5 %"))
      (libsource (lib "MareLux24Lib") (part "RES_GEN_SMD"))
    )
    (comp (ref "R52")
      (value "100R")
      (footprint "MareLux24Lib:RES_0402_SMD")
      (description "Generic Chip Res 100R")
      (fields (field (name "PART NUMBER") "RMCF0402JT100R") (field (name "TOLERANCE") "5 %"))
      (libsource (lib "MareLux24Lib") (part "RES_GEN_SMD"))
    )
    (comp (ref "R53")
      (value "100k")
      (footprint "MareLux24Lib:RES_0402_SMD")
      (description "Generic Chip Res 158k")
      (fields (field (name "PART NUMBER") "RMCF0402JT100K") (field (name "TOLERANCE") "5%"))
      (libsource (lib "MareLux24Lib") (part "RES_GEN_SMD"))
    )
    (comp (ref "R54")
      (value "100R")
      (footprint "MareLux24Lib:RES_0402_SMD")
      (description "Generic Chip Res 100R")
      (fields (field (name "PART NUMBER") "RMCF0402JT100R") (field (name "TOLERANCE") "5 %"))
      (libsource (lib "MareLux24Lib") (part "RES_GEN_SMD"))
    )
    (comp (ref "R55")
      (value "100k")
      (footprint "MareLux24Lib:RES_0402_SMD")
      (description "Generic Chip Res 158k")
      (fields (field (name "PART NUMBER") "RMCF0402JT100K") (field (name "TOLERANCE") "5%"))
      (libsource (lib "MareLux24Lib") (part "RES_GEN_SMD"))
    )
    (comp (ref "R56")
      (value "100R")
      (footprint "MareLux24Lib:RES_0402_SMD")
      (description "Generic Chip Res 100R")
      (fields (field (name "PART NUMBER") "RMCF0402JT100R") (field (name "TOLERANCE") "5 %"))
      (libsource (lib "MareLux24Lib") (part "RES_GEN_SMD"))
    )
    (comp (ref "R57")
      (value "100k")
      (footprint "MareLux24Lib:RES_0402_SMD")
      (description "Generic Chip Res 158k")
      (fields (field (name "PART NUMBER") "RMCF0402JT100K") (field (name "TOLERANCE") "5%"))
      (libsource (lib "MareLux24Lib") (part "RES_GEN_SMD"))
    )
    (comp (ref "R58")
      (value "100R")
      (footprint "MareLux24Lib:RES_0402_SMD")
      (description "Generic Chip Res 100R")
      (fields (field (name "PART NUMBER") "RMCF0402JT100R") (field (name "TOLERANCE") "5 %"))
      (libsource (lib "MareLux24Lib") (part "RES_GEN_SMD"))
    )
    (comp (ref "R59")
      (value "100R")
      (footprint "MareLux24Lib:RES_0402_SMD")
      (description "Generic Chip Res 100R")
      (fields (field (name "PART NUMBER") "RMCF0402JT100R") (field (name "TOLERANCE") "5 %"))
      (libsource (lib "MareLux24Lib") (part "RES_GEN_SMD"))
    )
    (comp (ref "R60")
      (value "100R")
      (footprint "MareLux24Lib:RES_0402_SMD")
      (description "Generic Chip Res 100R")
      (fields (field (name "PART NUMBER") "RMCF0402JT100R") (field (name "TOLERANCE") "5 %"))
      (libsource (lib "MareLux24Lib") (part "RES_GEN_SMD"))
    )
    (comp (ref "R61")
      (value "100R")
      (footprint "MareLux24Lib:RES_0402_SMD")
      (description "Generic Chip Res 100R")
      (fields (field (name "PART NUMBER") "RMCF0402JT100R") (field (name "TOLERANCE") "5 %"))
      (libsource (lib "MareLux24Lib") (part "RES_GEN_SMD"))
    )
    (comp (ref "R62")
      (value "100R")
      (footprint "MareLux24Lib:RES_0402_SMD")
      (description "Generic Chip Res 100R")
      (fields (field (name "PART NUMBER") "RMCF0402JT100R") (field (name "TOLERANCE") "5 %"))
      (libsource (lib "MareLux24Lib") (part "RES_GEN_SMD"))
    )
    (comp (ref "R63")
      (value "100R")
      (footprint "MareLux24Lib:RES_0402_SMD")
      (description "Generic Chip Res 100R")
      (fields (field (name "PART NUMBER") "RMCF0402JT100R") (field (name "TOLERANCE") "5 %"))
      (libsource (lib "MareLux24Lib") (part "RES_GEN_SMD"))
    )
    (comp (ref "R64")
      (value "100R")
      (footprint "MareLux24Lib:RES_0402_SMD")
      (description "Generic Chip Res 100R")
      (fields (field (name "PART NUMBER") "RMCF0402JT100R") (field (name "TOLERANCE") "5 %"))
      (libsource (lib "MareLux24Lib") (part "RES_GEN_SMD"))
    )
    (comp (ref "R65")
      (value "100k")
      (footprint "MareLux24Lib:RES_0402_SMD")
      (description "Generic Chip Res 158k")
      (fields (field (name "PART NUMBER") "RMCF0402JT100K") (field (name "TOLERANCE") "5%"))
      (libsource (lib "MareLux24Lib") (part "RES_GEN_SMD"))
    )
    (comp (ref "R66")
      (value "100R")
      (footprint "MareLux24Lib:RES_0402_SMD")
      (description "Generic Chip Res 100R")
      (fields (field (name "PART NUMBER") "RMCF0402JT100R") (field (name "TOLERANCE") "5 %"))
      (libsource (lib "MareLux24Lib") (part "RES_GEN_SMD"))
    )
    (comp (ref "R67")
      (value "100k")
      (footprint "MareLux24Lib:RES_0402_SMD")
      (description "Generic Chip Res 158k")
      (fields (field (name "PART NUMBER") "RMCF0402JT100K") (field (name "TOLERANCE") "5%"))
      (libsource (lib "MareLux24Lib") (part "RES_GEN_SMD"))
    )
    (comp (ref "R68")
      (value "100R")
      (footprint "MareLux24Lib:RES_0402_SMD")
      (description "Generic Chip Res 100R")
      (fields (field (name "PART NUMBER") "RMCF0402JT100R") (field (name "TOLERANCE") "5 %"))
      (libsource (lib "MareLux24Lib") (part "RES_GEN_SMD"))
    )
    (comp (ref "R69")
      (value "100k")
      (footprint "MareLux24Lib:RES_0402_SMD")
      (description "Generic Chip Res 158k")
      (fields (field (name "PART NUMBER") "RMCF0402JT100K") (field (name "TOLERANCE") "5%"))
      (libsource (lib "MareLux24Lib") (part "RES_GEN_SMD"))
    )
    (comp (ref "R70")
      (value "100R")
      (footprint "MareLux24Lib:RES_0402_SMD")
      (description "Generic Chip Res 100R")
      (fields (field (name "PART NUMBER") "RMCF0402JT100R") (field (name "TOLERANCE") "5 %"))
      (libsource (lib "MareLux24Lib") (part "RES_GEN_SMD"))
    )
    (comp (ref "R71")
      (value "100R")
      (footprint "MareLux24Lib:RES_0402_SMD")
      (description "Generic Chip Res 100R")
      (fields (field (name "PART NUMBER") "RMCF0402JT100R") (field (name "TOLERANCE") "5 %"))
      (libsource (lib "MareLux24Lib") (part "RES_GEN_SMD"))
    )
    (comp (ref "R72")
      (value "100R")
      (footprint "MareLux24Lib:RES_0402_SMD")
      (description "Generic Chip Res 100R")
      (fields (field (name "PART NUMBER") "RMCF0402JT100R") (field (name "TOLERANCE") "5 %"))
      (libsource (lib "MareLux24Lib") (part "RES_GEN_SMD"))
    )
    (comp (ref "R73")
      (value "100R")
      (footprint "MareLux24Lib:RES_0402_SMD")
      (description "Generic Chip Res 100R")
      (fields (field (name "PART NUMBER") "RMCF0402JT100R") (field (name "TOLERANCE") "5 %"))
      (libsource (lib "MareLux24Lib") (part "RES_GEN_SMD"))
    )
    (comp (ref "R74")
      (value "100R")
      (footprint "MareLux24Lib:RES_0402_SMD")
      (description "Generic Chip Res 100R")
      (fields (field (name "PART NUMBER") "RMCF0402JT100R") (field (name "TOLERANCE") "5 %"))
      (libsource (lib "MareLux24Lib") (part "RES_GEN_SMD"))
    )
    (comp (ref "R75")
      (value "100R")
      (footprint "MareLux24Lib:RES_0402_SMD")
      (description "Generic Chip Res 100R")
      (fields (field (name "PART NUMBER") "RMCF0402JT100R") (field (name "TOLERANCE") "5 %"))
      (libsource (lib "MareLux24Lib") (part "RES_GEN_SMD"))
    )
    (comp (ref "R76")
      (value "100R")
      (footprint "MareLux24Lib:RES_0402_SMD")
      (description "Generic Chip Res 100R")
      (fields (field (name "PART NUMBER") "RMCF0402JT100R") (field (name "TOLERANCE") "5 %"))
      (libsource (lib "MareLux24Lib") (part "RES_GEN_SMD"))
    )
    (comp (ref "R77")
      (value "100k")
      (footprint "MareLux24Lib:RES_0402_SMD")
      (description "Generic Chip Res 158k")
      (fields (field (name "PART NUMBER") "RMCF0402JT100K") (field (name "TOLERANCE") "5%"))
      (libsource (lib "MareLux24Lib") (part "RES_GEN_SMD"))
    )
    (comp (ref "R78")
      (value "100R")
      (footprint "MareLux24Lib:RES_0402_SMD")
      (description "Generic Chip Res 100R")
      (fields (field (name "PART NUMBER") "RMCF0402JT100R") (field (name "TOLERANCE") "5 %"))
      (libsource (lib "MareLux24Lib") (part "RES_GEN_SMD"))
    )
    (comp (ref "R79")
      (value "100k")
      (footprint "MareLux24Lib:RES_0402_SMD")
      (description "Generic Chip Res 158k")
      (fields (field (name "PART NUMBER") "RMCF0402JT100K") (field (name "TOLERANCE") "5%"))
      (libsource (lib "MareLux24Lib") (part "RES_GEN_SMD"))
    )
    (comp (ref "R80")
      (value "100R")
      (footprint "MareLux24Lib:RES_0402_SMD")
      (description "Generic Chip Res 100R")
      (fields (field (name "PART NUMBER") "RMCF0402JT100R") (field (name "TOLERANCE") "5 %"))
      (libsource (lib "MareLux24Lib") (part "RES_GEN_SMD"))
    )
    (comp (ref "R81")
      (value "100k")
      (footprint "MareLux24Lib:RES_0402_SMD")
      (description "Generic Chip Res 158k")
      (fields (field (name "PART NUMBER") "RMCF0402JT100K") (field (name "TOLERANCE") "5%"))
      (libsource (lib "MareLux24Lib") (part "RES_GEN_SMD"))
    )
    (comp (ref "R82")
      (value "100R")
      (footprint "MareLux24Lib:RES_0402_SMD")
      (description "Generic Chip Res 100R")
      (fields (field (name "PART NUMBER") "RMCF0402JT100R") (field (name "TOLERANCE") "5 %"))
      (libsource (lib "MareLux24Lib") (part "RES_GEN_SMD"))
    )
    (comp (ref "R83")
      (value "100R")
      (footprint "MareLux24Lib:RES_0402_SMD")
      (description "Generic Chip Res 100R")
      (fields (field (name "PART NUMBER") "RMCF0402JT100R") (field (name "TOLERANCE") "5 %"))
      (libsource (lib "MareLux24Lib") (part "RES_GEN_SMD"))
    )
    (comp (ref "R84")
      (value "100R")
      (footprint "MareLux24Lib:RES_0402_SMD")
      (description "Generic Chip Res 100R")
      (fields (field (name "PART NUMBER") "RMCF0402JT100R") (field (name "TOLERANCE") "5 %"))
      (libsource (lib "MareLux24Lib") (part "RES_GEN_SMD"))
    )
    (comp (ref "R85")
      (value "100R")
      (footprint "MareLux24Lib:RES_0402_SMD")
      (description "Generic Chip Res 100R")
      (fields (field (name "PART NUMBER") "RMCF0402JT100R") (field (name "TOLERANCE") "5 %"))
      (libsource (lib "MareLux24Lib") (part "RES_GEN_SMD"))
    )
    (comp (ref "R86")
      (value "100R")
      (footprint "MareLux24Lib:RES_0402_SMD")
      (description "Generic Chip Res 100R")
      (fields (field (name "PART NUMBER") "RMCF0402JT100R") (field (name "TOLERANCE") "5 %"))
      (libsource (lib "MareLux24Lib") (part "RES_GEN_SMD"))
    )
    (comp (ref "R87")
      (value "100R")
      (footprint "MareLux24Lib:RES_0402_SMD")
      (description "Generic Chip Res 100R")
      (fields (field (name "PART NUMBER") "RMCF0402JT100R") (field (name "TOLERANCE") "5 %"))
      (libsource (lib "MareLux24Lib") (part "RES_GEN_SMD"))
    )
    (comp (ref "R88")
      (value "100R")
      (footprint "MareLux24Lib:RES_0402_SMD")
      (description "Generic Chip Res 100R")
      (fields (field (name "PART NUMBER") "RMCF0402JT100R") (field (name "TOLERANCE") "5 %"))
      (libsource (lib "MareLux24Lib") (part "RES_GEN_SMD"))
    )
    (comp (ref "R89")
      (value "100k")
      (footprint "MareLux24Lib:RES_0402_SMD")
      (description "Generic Chip Res 158k")
      (fields (field (name "PART NUMBER") "RMCF0402JT100K") (field (name "TOLERANCE") "5%"))
      (libsource (lib "MareLux24Lib") (part "RES_GEN_SMD"))
    )
    (comp (ref "R90")
      (value "100R")
      (footprint "MareLux24Lib:RES_0402_SMD")
      (description "Generic Chip Res 100R")
      (fields (field (name "PART NUMBER") "RMCF0402JT100R") (field (name "TOLERANCE") "5 %"))
      (libsource (lib "MareLux24Lib") (part "RES_GEN_SMD"))
    )
    (comp (ref "R91")
      (value "100k")
      (footprint "MareLux24Lib:RES_0402_SMD")
      (description "Generic Chip Res 158k")
      (fields (field (name "PART NUMBER") "RMCF0402JT100K") (field (name "TOLERANCE") "5%"))
      (libsource (lib "MareLux24Lib") (part "RES_GEN_SMD"))
    )
    (comp (ref "R92")
      (value "100R")
      (footprint "MareLux24Lib:RES_0402_SMD")
      (description "Generic Chip Res 100R")
      (fields (field (name "PART NUMBER") "RMCF0402JT100R") (field (name "TOLERANCE") "5 %"))
      (libsource (lib "MareLux24Lib") (part "RES_GEN_SMD"))
    )
    (comp (ref "R93")
      (value "100k")
      (footprint "MareLux24Lib:RES_0402_SMD")
      (description "Generic Chip Res 158k")
      (fields (field (name "PART NUMBER") "RMCF0402JT100K") (field (name "TOLERANCE") "5%"))
      (libsource (lib "MareLux24Lib") (part "RES_GEN_SMD"))
    )
    (comp (ref "R94")
      (value "100R")
      (footprint "MareLux24Lib:RES_0402_SMD")
      (description "Generic Chip Res 100R")
      (fields (field (name "PART NUMBER") "RMCF0402JT100R") (field (name "TOLERANCE") "5 %"))
      (libsource (lib "MareLux24Lib") (part "RES_GEN_SMD"))
    )
    (comp (ref "R95")
      (value "100R")
      (footprint "MareLux24Lib:RES_0402_SMD")
      (description "Generic Chip Res 100R")
      (fields (field (name "PART NUMBER") "RMCF0402JT100R") (field (name "TOLERANCE") "5 %"))
      (libsource (lib "MareLux24Lib") (part "RES_GEN_SMD"))
    )
    (comp (ref "R96")
      (value "100R")
      (footprint "MareLux24Lib:RES_0402_SMD")
      (description "Generic Chip Res 100R")
      (fields (field (name "PART NUMBER") "RMCF0402JT100R") (field (name "TOLERANCE") "5 %"))
      (libsource (lib "MareLux24Lib") (part "RES_GEN_SMD"))
    )
    (comp (ref "R97")
      (value "100R")
      (footprint "MareLux24Lib:RES_0402_SMD")
      (description "Generic Chip Res 100R")
      (fields (field (name "PART NUMBER") "RMCF0402JT100R") (field (name "TOLERANCE") "5 %"))
      (libsource (lib "MareLux24Lib") (part "RES_GEN_SMD"))
    )
    (comp (ref "R98")
      (value "100R")
      (footprint "MareLux24Lib:RES_0402_SMD")
      (description "Generic Chip Res 100R")
      (fields (field (name "PART NUMBER") "RMCF0402JT100R") (field (name "TOLERANCE") "5 %"))
      (libsource (lib "MareLux24Lib") (part "RES_GEN_SMD"))
    )
    (comp (ref "R99")
      (value "100R")
      (footprint "MareLux24Lib:RES_0402_SMD")
      (description "Generic Chip Res 100R")
      (fields (field (name "PART NUMBER") "RMCF0402JT100R") (field (name "TOLERANCE") "5 %"))
      (libsource (lib "MareLux24Lib") (part "RES_GEN_SMD"))
    )
    (comp (ref "R100")
      (value "100R")
      (footprint "MareLux24Lib:RES_0402_SMD")
      (description "Generic Chip Res 100R")
      (fields (field (name "PART NUMBER") "RMCF0402JT100R") (field (name "TOLERANCE") "5 %"))
      (libsource (lib "MareLux24Lib") (part "RES_GEN_SMD"))
    )
    (comp (ref "R101")
      (value "100k")
      (footprint "MareLux24Lib:RES_0402_SMD")
      (description "Generic Chip Res 158k")
      (fields (field (name "PART NUMBER") "RMCF0402JT100K") (field (name "TOLERANCE") "5%"))
      (libsource (lib "MareLux24Lib") (part "RES_GEN_SMD"))
    )
    (comp (ref "R102")
      (value "100R")
      (footprint "MareLux24Lib:RES_0402_SMD")
      (description "Generic Chip Res 100R")
      (fields (field (name "PART NUMBER") "RMCF0402JT100R") (field (name "TOLERANCE") "5 %"))
      (libsource (lib "MareLux24Lib") (part "RES_GEN_SMD"))
    )
    (comp (ref "R103")
      (value "100k")
      (footprint "MareLux24Lib:RES_0402_SMD")
      (description "Generic Chip Res 158k")
      (fields (field (name "PART NUMBER") "RMCF0402JT100K") (field (name "TOLERANCE") "5%"))
      (libsource (lib "MareLux24Lib") (part "RES_GEN_SMD"))
    )
    (comp (ref "R104")
      (value "100R")
      (footprint "MareLux24Lib:RES_0402_SMD")
      (description "Generic Chip Res 100R")
      (fields (field (name "PART NUMBER") "RMCF0402JT100R") (field (name "TOLERANCE") "5 %"))
      (libsource (lib "MareLux24Lib") (part "RES_GEN_SMD"))
    )
    (comp (ref "R105")
      (value "100k")
      (footprint "MareLux24Lib:RES_0402_SMD")
      (description "Generic Chip Res 158k")
      (fields (field (name "PART NUMBER") "RMCF0402JT100K") (field (name "TOLERANCE") "5%"))
      (libsource (lib "MareLux24Lib") (part "RES_GEN_SMD"))
    )
    (comp (ref "R106")
      (value "100R")
      (footprint "MareLux24Lib:RES_0402_SMD")
      (description "Generic Chip Res 100R")
      (fields (field (name "PART NUMBER") "RMCF0402JT100R") (field (name "TOLERANCE") "5 %"))
      (libsource (lib "MareLux24Lib") (part "RES_GEN_SMD"))
    )
    (comp (ref "R107")
      (value "100R")
      (footprint "MareLux24Lib:RES_0402_SMD")
      (description "Generic Chip Res 100R")
      (fields (field (name "PART NUMBER") "RMCF0402JT100R") (field (name "TOLERANCE") "5 %"))
      (libsource (lib "MareLux24Lib") (part "RES_GEN_SMD"))
    )
    (comp (ref "R108")
      (value "100R")
      (footprint "MareLux24Lib:RES_0402_SMD")
      (description "Generic Chip Res 100R")
      (fields (field (name "PART NUMBER") "RMCF0402JT100R") (field (name "TOLERANCE") "5 %"))
      (libsource (lib "MareLux24Lib") (part "RES_GEN_SMD"))
    )
  )
  (nets
    (net (code "1") (name "/BOOT_0") (class "Default")
      (node (ref "J_EXTRA") (pin "4") (pinfunction "4_4") (pintype "passive"))
    )
    (net (code "2") (name "/EN_SENSOR-1") (class "Default")
      (node (ref "R10") (pin "2") (pinfunction "2_2") (pintype "passive+no_connect"))
    )
    (net (code "3") (name "/EN_SENSOR-2") (class "Default")
      (node (ref "R11") (pin "2") (pinfunction "2_2") (pintype "passive"))
    )
    (net (code "4") (name "/EN_SENSOR-3") (class "Default")
      (node (ref "R12") (pin "2") (pinfunction "2_2") (pintype "passive"))
    )
    (net (code "5") (name "/EN_SENSOR-4") (class "Default")
      (node (ref "R22") (pin "2") (pinfunction "2_2") (pintype "passive"))
    )
    (net (code "6") (name "/EN_SENSOR-5") (class "Default")
      (node (ref "R23") (pin "2") (pinfunction "2_2") (pintype "passive"))
    )
    (net (code "7") (name "/EN_SENSOR-6") (class "Default")
      (node (ref "R24") (pin "2") (pinfunction "2_2") (pintype "passive"))
    )
    (net (code "8") (name "/EN_SENSOR-7") (class "Default")
      (node (ref "R34") (pin "2") (pinfunction "2_2") (pintype "passive"))
    )
    (net (code "9") (name "/EN_SENSOR-8") (class "Default")
      (node (ref "R35") (pin "2") (pinfunction "2_2") (pintype "passive"))
    )
    (net (code "10") (name "/EN_SENSOR-9") (class "Default")
      (node (ref "R36") (pin "2") (pinfunction "2_2") (pintype "passive"))
    )
    (net (code "11") (name "/EN_SENSOR-10") (class "Default")
      (node (ref "R46") (pin "2") (pinfunction "2_2") (pintype "passive"))
    )
    (net (code "12") (name "/EN_SENSOR-11") (class "Default")
      (node (ref "R47") (pin "2") (pinfunction "2_2") (pintype "passive"))
    )
    (net (code "13") (name "/EN_SENSOR-12") (class "Default")
      (node (ref "R48") (pin "2") (pinfunction "2_2") (pintype "passive"))
    )
    (net (code "14") (name "/EN_SENSOR-13") (class "Default")
      (node (ref "R58") (pin "2") (pinfunction "2_2") (pintype "passive"))
    )
    (net (code "15") (name "/EN_SENSOR-14") (class "Default")
      (node (ref "R59") (pin "2") (pinfunction "2_2") (pintype "passive"))
    )
    (net (code "16") (name "/EN_SENSOR-15") (class "Default")
      (node (ref "R60") (pin "2") (pinfunction "2_2") (pintype "passive"))
    )
    (net (code "17") (name "/EN_SENSOR-16") (class "Default")
      (node (ref "R70") (pin "2") (pinfunction "2_2") (pintype "passive"))
    )
    (net (code "18") (name "/EN_SENSOR-17") (class "Default")
      (node (ref "R71") (pin "2") (pinfunction "2_2") (pintype "passive"))
    )
    (net (code "19") (name "/EN_SENSOR-18") (class "Default")
      (node (ref "R72") (pin "2") (pinfunction "2_2") (pintype "passive"))
    )
    (net (code "20") (name "/EN_SENSOR-19") (class "Default")
      (node (ref "R82") (pin "2") (pinfunction "2_2") (pintype "passive"))
    )
    (net (code "21") (name "/EN_SENSOR-20") (class "Default")
      (node (ref "R83") (pin "2") (pinfunction "2_2") (pintype "passive"))
    )
    (net (code "22") (name "/EN_SENSOR-21") (class "Default")
      (node (ref "R84") (pin "2") (pinfunction "2_2") (pintype "passive"))
    )
    (net (code "23") (name "/EN_SENSOR-22") (class "Default")
      (node (ref "R94") (pin "2") (pinfunction "2_2") (pintype "passive"))
    )
    (net (code "24") (name "/EN_SENSOR-23") (class "Default")
      (node (ref "R95") (pin "2") (pinfunction "2_2") (pintype "passive"))
    )
    (net (code "25") (name "/EN_SENSOR-24") (class "Default")
      (node (ref "R96") (pin "2") (pinfunction "2_2") (pintype "passive"))
    )
    (net (code "26") (name "/EN_SENSOR-25") (class "Default")
      (node (ref "R106") (pin "2") (pinfunction "2_2") (pintype "passive"))
    )
    (net (code "27") (name "/EN_SENSOR-26") (class "Default")
      (node (ref "R107") (pin "2") (pinfunction "2_2") (pintype "passive"))
    )
    (net (code "28") (name "/EN_SENSOR-27") (class "Default")
      (node (ref "R108") (pin "2") (pinfunction "2_2") (pintype "passive"))
    )
    (net (code "29") (name "/GPIO_CH-1") (class "Default")
      (node (ref "J1") (pin "3") (pinfunction "3_3") (pintype "passive"))
    )
    (net (code "30") (name "/GPIO_CH-2") (class "Default")
      (node (ref "J2") (pin "3") (pinfunction "3_3") (pintype "passive"))
    )
    (net (code "31") (name "/GPIO_CH-3") (class "Default")
      (node (ref "J3") (pin "3") (pinfunction "3_3") (pintype "passive"))
    )
    (net (code "32") (name "/GPIO_CH-4") (class "Default")
      (node (ref "J4") (pin "3") (pinfunction "3_3") (pintype "passive"))
    )
    (net (code "33") (name "/GPIO_CH-5") (class "Default")
      (node (ref "J5") (pin "3") (pinfunction "3_3") (pintype "passive"))
    )
    (net (code "34") (name "/GPIO_CH-6") (class "Default")
      (node (ref "J6") (pin "3") (pinfunction "3_3") (pintype "passive"))
    )
    (net (code "35") (name "/GPIO_CH-7") (class "Default")
      (node (ref "J7") (pin "3") (pinfunction "3_3") (pintype "passive"))
    )
    (net (code "36") (name "/GPIO_CH-8") (class "Default")
      (node (ref "J8") (pin "3") (pinfunction "3_3") (pintype "passive"))
    )
    (net (code "37") (name "/GPIO_CH-9") (class "Default")
      (node (ref "J9") (pin "3") (pinfunction "3_3") (pintype "passive"))
    )
    (net (code "38") (name "/GPIO_CH-10") (class "Default")
      (node (ref "J10") (pin "3") (pinfunction "3_3") (pintype "passive"))
    )
    (net (code "39") (name "/GPIO_CH-11") (class "Default")
      (node (ref "J11") (pin "3") (pinfunction "3_3") (pintype "passive"))
    )
    (net (code "40") (name "/GPIO_CH-12") (class "Default")
      (node (ref "J12") (pin "3") (pinfunction "3_3") (pintype "passive"))
    )
    (net (code "41") (name "/GPIO_CH-13") (class "Default")
      (node (ref "J13") (pin "3") (pinfunction "3_3") (pintype "passive"))
    )
    (net (code "42") (name "/GPIO_CH-14") (class "Default")
      (node (ref "J14") (pin "3") (pinfunction "3_3") (pintype "passive"))
    )
    (net (code "43") (name "/GPIO_CH-15") (class "Default")
      (node (ref "J15") (pin "3") (pinfunction "3_3") (pintype "passive"))
    )
    (net (code "44") (name "/GPIO_CH-16") (class "Default")
      (node (ref "J16") (pin "3") (pinfunction "3_3") (pintype "passive"))
    )
    (net (code "45") (name "/GPIO_CH-17") (class "Default")
      (node (ref "J17") (pin "3") (pinfunction "3_3") (pintype "passive"))
    )
    (net (code "46") (name "/GPIO_CH-18") (class "Default")
      (node (ref "J18") (pin "3") (pinfunction "3_3") (pintype "passive"))
    )
    (net (code "47") (name "/GPIO_CH-19") (class "Default")
      (node (ref "J19") (pin "3") (pinfunction "3_3") (pintype "passive"))
    )
    (net (code "48") (name "/GPIO_CH-20") (class "Default")
      (node (ref "J20") (pin "3") (pinfunction "3_3") (pintype "passive"))
    )
    (net (code "49") (name "/GPIO_CH-21") (class "Default")
      (node (ref "J21") (pin "3") (pinfunction "3_3") (pintype "passive"))
    )
    (net (code "50") (name "/GPIO_CH-22") (class "Default")
      (node (ref "J22") (pin "3") (pinfunction "3_3") (pintype "passive"))
    )
    (net (code "51") (name "/GPIO_CH-23") (class "Default")
      (node (ref "J23") (pin "3") (pinfunction "3_3") (pintype "passive"))
    )
    (net (code "52") (name "/GPIO_CH-24") (class "Default")
      (node (ref "J24") (pin "3") (pinfunction "3_3") (pintype "passive"))
    )
    (net (code "53") (name "/GPIO_CH-25") (class "Default")
      (node (ref "J25") (pin "3") (pinfunction "3_3") (pintype "passive"))
    )
    (net (code "54") (name "/GPIO_CH-26") (class "Default")
      (node (ref "J26") (pin "3") (pinfunction "3_3") (pintype "passive"))
    )
    (net (code "55") (name "/GPIO_CH-27") (class "Default")
      (node (ref "J27") (pin "3") (pinfunction "3_3") (pintype "passive"))
    )
    (net (code "56") (name "/I2C_SCL-4") (class "Default")
      (node (ref "J_EXTRA") (pin "7") (pinfunction "7_7") (pintype "passive"))
    )
    (net (code "57") (name "/I2C_SDA-4") (class "Default")
      (node (ref "J_EXTRA") (pin "6") (pinfunction "6_6") (pintype "passive"))
    )
    (net (code "58") (name "/PG_CH-1") (class "Default")
      (node (ref "J1") (pin "5") (pinfunction "5_5") (pintype "passive"))
    )
    (net (code "59") (name "/PG_CH-2") (class "Default")
      (node (ref "J2") (pin "5") (pinfunction "5_5") (pintype "passive"))
    )
    (net (code "60") (name "/PG_CH-3") (class "Default")
      (node (ref "J3") (pin "5") (pinfunction "5_5") (pintype "passive"))
    )
    (net (code "61") (name "/PG_CH-4") (class "Default")
      (node (ref "J4") (pin "5") (pinfunction "5_5") (pintype "passive"))
    )
    (net (code "62") (name "/PG_CH-5") (class "Default")
      (node (ref "J5") (pin "5") (pinfunction "5_5") (pintype "passive"))
    )
    (net (code "63") (name "/PG_CH-6") (class "Default")
      (node (ref "J6") (pin "5") (pinfunction "5_5") (pintype "passive"))
    )
    (net (code "64") (name "/PG_CH-7") (class "Default")
      (node (ref "J7") (pin "5") (pinfunction "5_5") (pintype "passive"))
    )
    (net (code "65") (name "/PG_CH-8") (class "Default")
      (node (ref "J8") (pin "5") (pinfunction "5_5") (pintype "passive"))
    )
    (net (code "66") (name "/PG_CH-9") (class "Default")
      (node (ref "J9") (pin "5") (pinfunction "5_5") (pintype "passive"))
    )
    (net (code "67") (name "/PG_CH-10") (class "Default")
      (node (ref "J10") (pin "5") (pinfunction "5_5") (pintype "passive"))
    )
    (net (code "68") (name "/PG_CH-11") (class "Default")
      (node (ref "J11") (pin "5") (pinfunction "5_5") (pintype "passive"))
    )
    (net (code "69") (name "/PG_CH-12") (class "Default")
      (node (ref "J12") (pin "5") (pinfunction "5_5") (pintype "passive"))
    )
    (net (code "70") (name "/PG_CH-13") (class "Default")
      (node (ref "J13") (pin "5") (pinfunction "5_5") (pintype "passive"))
    )
    (net (code "71") (name "/PG_CH-14") (class "Default")
      (node (ref "J14") (pin "5") (pinfunction "5_5") (pintype "passive"))
    )
    (net (code "72") (name "/PG_CH-15") (class "Default")
      (node (ref "J15") (pin "5") (pinfunction "5_5") (pintype "passive"))
    )
    (net (code "73") (name "/PG_CH-16") (class "Default")
      (node (ref "J16") (pin "5") (pinfunction "5_5") (pintype "passive"))
    )
    (net (code "74") (name "/PG_CH-17") (class "Default")
      (node (ref "J17") (pin "5") (pinfunction "5_5") (pintype "passive"))
    )
    (net (code "75") (name "/PG_CH-18") (class "Default")
      (node (ref "J18") (pin "5") (pinfunction "5_5") (pintype "passive"))
    )
    (net (code "76") (name "/PG_CH-19") (class "Default")
      (node (ref "J19") (pin "5") (pinfunction "5_5") (pintype "passive"))
    )
    (net (code "77") (name "/PG_CH-20") (class "Default")
      (node (ref "J20") (pin "5") (pinfunction "5_5") (pintype "passive"))
    )
    (net (code "78") (name "/PG_CH-21") (class "Default")
      (node (ref "J21") (pin "5") (pinfunction "5_5") (pintype "passive"))
    )
    (net (code "79") (name "/PG_CH-22") (class "Default")
      (node (ref "J22") (pin "5") (pinfunction "5_5") (pintype "passive"))
    )
    (net (code "80") (name "/PG_CH-23") (class "Default")
      (node (ref "J23") (pin "5") (pinfunction "5_5") (pintype "passive"))
    )
    (net (code "81") (name "/PG_CH-24") (class "Default")
      (node (ref "J24") (pin "5") (pinfunction "5_5") (pintype "passive"))
    )
    (net (code "82") (name "/PG_CH-25") (class "Default")
      (node (ref "J25") (pin "5") (pinfunction "5_5") (pintype "passive"))
    )
    (net (code "83") (name "/PG_CH-26") (class "Default")
      (node (ref "J26") (pin "5") (pinfunction "5_5") (pintype "passive"))
    )
    (net (code "84") (name "/PG_CH-27") (class "Default")
      (node (ref "J27") (pin "5") (pinfunction "5_5") (pintype "passive"))
    )
    (net (code "85") (name "/RS485_N") (class "Default")
      (node (ref "INPUT") (pin "3") (pinfunction "3_3") (pintype "passive"))
      (node (ref "INPUT2") (pin "3") (pinfunction "3_3") (pintype "passive"))
    )
    (net (code "86") (name "/RS485_P") (class "Default")
      (node (ref "INPUT") (pin "2") (pinfunction "2_2") (pintype "passive"))
      (node (ref "INPUT2") (pin "2") (pinfunction "2_2") (pintype "passive"))
    )
    (net (code "87") (name "/SCL_CH-1") (class "Default")
      (node (ref "R4") (pin "2") (pinfunction "2_2") (pintype "passive"))
    )
    (net (code "88") (name "/SCL_CH-2") (class "Default")
      (node (ref "R6") (pin "2") (pinfunction "2_2") (pintype "passive"))
    )
    (net (code "89") (name "/SCL_CH-3") (class "Default")
      (node (ref "R8") (pin "2") (pinfunction "2_2") (pintype "passive"))
    )
    (net (code "90") (name "/SCL_CH-4") (class "Default")
      (node (ref "R16") (pin "2") (pinfunction "2_2") (pintype "passive"))
    )
    (net (code "91") (name "/SCL_CH-5") (class "Default")
      (node (ref "R18") (pin "2") (pinfunction "2_2") (pintype "passive"))
    )
    (net (code "92") (name "/SCL_CH-6") (class "Default")
      (node (ref "R20") (pin "2") (pinfunction "2_2") (pintype "passive"))
    )
    (net (code "93") (name "/SCL_CH-7") (class "Default")
      (node (ref "R28") (pin "2") (pinfunction "2_2") (pintype "passive"))
    )
    (net (code "94") (name "/SCL_CH-8") (class "Default")
      (node (ref "R30") (pin "2") (pinfunction "2_2") (pintype "passive"))
    )
    (net (code "95") (name "/SCL_CH-9") (class "Default")
      (node (ref "R32") (pin "2") (pinfunction "2_2") (pintype "passive+no_connect"))
    )
    (net (code "96") (name "/SCL_CH-10") (class "Default")
      (node (ref "R40") (pin "2") (pinfunction "2_2") (pintype "passive+no_connect"))
    )
    (net (code "97") (name "/SCL_CH-11") (class "Default")
      (node (ref "R42") (pin "2") (pinfunction "2_2") (pintype "passive"))
    )
    (net (code "98") (name "/SCL_CH-12") (class "Default")
      (node (ref "R44") (pin "2") (pinfunction "2_2") (pintype "passive+no_connect"))
    )
    (net (code "99") (name "/SCL_CH-13") (class "Default")
      (node (ref "R52") (pin "2") (pinfunction "2_2") (pintype "passive"))
    )
    (net (code "100") (name "/SCL_CH-14") (class "Default")
      (node (ref "R54") (pin "2") (pinfunction "2_2") (pintype "passive"))
    )
    (net (code "101") (name "/SCL_CH-15") (class "Default")
      (node (ref "R56") (pin "2") (pinfunction "2_2") (pintype "passive"))
    )
    (net (code "102") (name "/SCL_CH-16") (class "Default")
      (node (ref "R64") (pin "2") (pinfunction "2_2") (pintype "passive+no_connect"))
    )
    (net (code "103") (name "/SCL_CH-17") (class "Default")
      (node (ref "R66") (pin "2") (pinfunction "2_2") (pintype "passive"))
    )
    (net (code "104") (name "/SCL_CH-18") (class "Default")
      (node (ref "R68") (pin "2") (pinfunction "2_2") (pintype "passive"))
    )
    (net (code "105") (name "/SCL_CH-19") (class "Default")
      (node (ref "R76") (pin "2") (pinfunction "2_2") (pintype "passive+no_connect"))
    )
    (net (code "106") (name "/SCL_CH-20") (class "Default")
      (node (ref "R78") (pin "2") (pinfunction "2_2") (pintype "passive"))
    )
    (net (code "107") (name "/SCL_CH-21") (class "Default")
      (node (ref "R80") (pin "2") (pinfunction "2_2") (pintype "passive"))
    )
    (net (code "108") (name "/SCL_CH-22") (class "Default")
      (node (ref "R88") (pin "2") (pinfunction "2_2") (pintype "passive"))
    )
    (net (code "109") (name "/SCL_CH-23") (class "Default")
      (node (ref "R90") (pin "2") (pinfunction "2_2") (pintype "passive"))
    )
    (net (code "110") (name "/SCL_CH-24") (class "Default")
      (node (ref "R92") (pin "2") (pinfunction "2_2") (pintype "passive"))
    )
    (net (code "111") (name "/SCL_CH-25") (class "Default")
      (node (ref "R100") (pin "2") (pinfunction "2_2") (pintype "passive"))
    )
    (net (code "112") (name "/SCL_CH-26") (class "Default")
      (node (ref "R102") (pin "2") (pinfunction "2_2") (pintype "passive+no_connect"))
    )
    (net (code "113") (name "/SCL_CH-27") (class "Default")
      (node (ref "R104") (pin "2") (pinfunction "2_2") (pintype "passive"))
    )
    (net (code "114") (name "/SDA_CH-1") (class "Default")
      (node (ref "R1") (pin "2") (pinfunction "2_2") (pintype "passive"))
    )
    (net (code "115") (name "/SDA_CH-2") (class "Default")
      (node (ref "R2") (pin "2") (pinfunction "2_2") (pintype "passive"))
    )
    (net (code "116") (name "/SDA_CH-3") (class "Default")
      (node (ref "R3") (pin "2") (pinfunction "2_2") (pintype "passive"))
    )
    (net (code "117") (name "/SDA_CH-4") (class "Default")
      (node (ref "R13") (pin "2") (pinfunction "2_2") (pintype "passive"))
    )
    (net (code "118") (name "/SDA_CH-5") (class "Default")
      (node (ref "R14") (pin "2") (pinfunction "2_2") (pintype "passive"))
    )
    (net (code "119") (name "/SDA_CH-6") (class "Default")
      (node (ref "R15") (pin "2") (pinfunction "2_2") (pintype "passive+no_connect"))
    )
    (net (code "120") (name "/SDA_CH-7") (class "Default")
      (node (ref "R25") (pin "2") (pinfunction "2_2") (pintype "passive"))
    )
    (net (code "121") (name "/SDA_CH-8") (class "Default")
      (node (ref "R26") (pin "2") (pinfunction "2_2") (pintype "passive+no_connect"))
    )
    (net (code "122") (name "/SDA_CH-9") (class "Default")
      (node (ref "R27") (pin "2") (pinfunction "2_2") (pintype "passive"))
    )
    (net (code "123") (name "/SDA_CH-10") (class "Default")
      (node (ref "R37") (pin "2") (pinfunction "2_2") (pintype "passive"))
    )
    (net (code "124") (name "/SDA_CH-11") (class "Default")
      (node (ref "R38") (pin "2") (pinfunction "2_2") (pintype "passive"))
    )
    (net (code "125") (name "/SDA_CH-12") (class "Default")
      (node (ref "R39") (pin "2") (pinfunction "2_2") (pintype "passive"))
    )
    (net (code "126") (name "/SDA_CH-13") (class "Default")
      (node (ref "R49") (pin "2") (pinfunction "2_2") (pintype "passive"))
    )
    (net (code "127") (name "/SDA_CH-14") (class "Default")
      (node (ref "R50") (pin "2") (pinfunction "2_2") (pintype "passive"))
    )
    (net (code "128") (name "/SDA_CH-15") (class "Default")
      (node (ref "R51") (pin "2") (pinfunction "2_2") (pintype "passive"))
    )
    (net (code "129") (name "/SDA_CH-16") (class "Default")
      (node (ref "R61") (pin "2") (pinfunction "2_2") (pintype "passive"))
    )
    (net (code "130") (name "/SDA_CH-17") (class "Default")
      (node (ref "R62") (pin "2") (pinfunction "2_2") (pintype "passive"))
    )
    (net (code "131") (name "/SDA_CH-18") (class "Default")
      (node (ref "R63") (pin "2") (pinfunction "2_2") (pintype "passive"))
    )
    (net (code "132") (name "/SDA_CH-19") (class "Default")
      (node (ref "R73") (pin "2") (pinfunction "2_2") (pintype "passive+no_connect"))
    )
    (net (code "133") (name "/SDA_CH-20") (class "Default")
      (node (ref "R74") (pin "2") (pinfunction "2_2") (pintype "passive"))
    )
    (net (code "134") (name "/SDA_CH-21") (class "Default")
      (node (ref "R75") (pin "2") (pinfunction "2_2") (pintype "passive"))
    )
    (net (code "135") (name "/SDA_CH-22") (class "Default")
      (node (ref "R85") (pin "2") (pinfunction "2_2") (pintype "passive"))
    )
    (net (code "136") (name "/SDA_CH-23") (class "Default")
      (node (ref "R86") (pin "2") (pinfunction "2_2") (pintype "passive"))
    )
    (net (code "137") (name "/SDA_CH-24") (class "Default")
      (node (ref "R87") (pin "2") (pinfunction "2_2") (pintype "passive"))
    )
    (net (code "138") (name "/SDA_CH-25") (class "Default")
      (node (ref "R97") (pin "2") (pinfunction "2_2") (pintype "passive"))
    )
    (net (code "139") (name "/SDA_CH-26") (class "Default")
      (node (ref "R98") (pin "2") (pinfunction "2_2") (pintype "passive"))
    )
    (net (code "140") (name "/SDA_CH-27") (class "Default")
      (node (ref "R99") (pin "2") (pinfunction "2_2") (pintype "passive"))
    )
    (net (code "141") (name "/SWCLK_MCU") (class "Default")
      (node (ref "J_BOS") (pin "2") (pinfunction "2_2") (pintype "passive"))
    )
    (net (code "142") (name "/SWD_MCU") (class "Default")
      (node (ref "J_BOS") (pin "3") (pinfunction "3_3") (pintype "passive"))
    )
    (net (code "143") (name "/UART_4_RX") (class "Default")
      (node (ref "J_EXTRA") (pin "3") (pinfunction "3_3") (pintype "passive"))
    )
    (net (code "144") (name "/UART_4_TX") (class "Default")
      (node (ref "J_EXTRA") (pin "2") (pinfunction "2_2") (pintype "passive"))
    )
    (net (code "145") (name "/nRST_MCU") (class "Default")
      (node (ref "J_BOS") (pin "4") (pinfunction "4_4") (pintype "passive"))
    )
    (net (code "146") (name "3V3_INT") (class "Default")
      (node (ref "Q1") (pin "2") (pinfunction "S_2") (pintype "passive"))
      (node (ref "Q10") (pin "2") (pinfunction "S_2") (pintype "passive"))
      (node (ref "Q11") (pin "2") (pinfunction "S_2") (pintype "passive"))
      (node (ref "Q12") (pin "2") (pinfunction "S_2") (pintype "passive"))
      (node (ref "Q13") (pin "2") (pinfunction "S_2") (pintype "passive"))
      (node (ref "Q14") (pin "2") (pinfunction "S_2") (pintype "passive"))
      (node (ref "Q15") (pin "2") (pinfunction "S_2") (pintype "passive"))
      (node (ref "Q16") (pin "2") (pinfunction "S_2") (pintype "passive"))
      (node (ref "Q17") (pin "2") (pinfunction "S_2") (pintype "passive"))
      (node (ref "Q18") (pin "2") (pinfunction "S_2") (pintype "passive"))
      (node (ref "Q19") (pin "2") (pinfunction "S_2") (pintype "passive"))
      (node (ref "Q2") (pin "2") (pinfunction "S_2") (pintype "passive"))
      (node (ref "Q20") (pin "2") (pinfunction "S_2") (pintype "passive"))
      (node (ref "Q21") (pin "2") (pinfunction "S_2") (pintype "passive"))
      (node (ref "Q22") (pin "2") (pinfunction "S_2") (pintype "passive"))
      (node (ref "Q23") (pin "2") (pinfunction "S_2") (pintype "passive"))
      (node (ref "Q24") (pin "2") (pinfunction "S_2") (pintype "passive"))
      (node (ref "Q25") (pin "2") (pinfunction "S_2") (pintype "passive"))
      (node (ref "Q26") (pin "2") (pinfunction "S_2") (pintype "passive"))
      (node (ref "Q27") (pin "2") (pinfunction "S_2") (pintype "passive"))
      (node (ref "Q3") (pin "2") (pinfunction "S_2") (pintype "passive"))
      (node (ref "Q4") (pin "2") (pinfunction "S_2") (pintype "passive"))
      (node (ref "Q5") (pin "2") (pinfunction "S_2") (pintype "passive"))
      (node (ref "Q6") (pin "2") (pinfunction "S_2") (pintype "passive"))
      (node (ref "Q7") (pin "2") (pinfunction "S_2") (pintype "passive"))
      (node (ref "Q8") (pin "2") (pinfunction "S_2") (pintype "passive"))
      (node (ref "Q9") (pin "2") (pinfunction "S_2") (pintype "passive"))
      (node (ref "R101") (pin "2") (pinfunction "2_2") (pintype "passive"))
      (node (ref "R103") (pin "2") (pinfunction "2_2") (pintype "passive"))
      (node (ref "R105") (pin "2") (pinfunction "2_2") (pintype "passive"))
      (node (ref "R17") (pin "2") (pinfunction "2_2") (pintype "passive"))
      (node (ref "R19") (pin "2") (pinfunction "2_2") (pintype "passive"))
      (node (ref "R21") (pin "2") (pinfunction "2_2") (pintype "passive"))
      (node (ref "R29") (pin "2") (pinfunction "2_2") (pintype "passive"))
      (node (ref "R31") (pin "2") (pinfunction "2_2") (pintype "passive"))
      (node (ref "R33") (pin "2") (pinfunction "2_2") (pintype "passive"))
      (node (ref "R41") (pin "2") (pinfunction "2_2") (pintype "passive"))
      (node (ref "R43") (pin "2") (pinfunction "2_2") (pintype "passive"))
      (node (ref "R45") (pin "2") (pinfunction "2_2") (pintype "passive"))
      (node (ref "R5") (pin "2") (pinfunction "2_2") (pintype "passive"))
      (node (ref "R53") (pin "2") (pinfunction "2_2") (pintype "passive"))
      (node (ref "R55") (pin "2") (pinfunction "2_2") (pintype "passive"))
      (node (ref "R57") (pin "2") (pinfunction "2_2") (pintype "passive"))
      (node (ref "R65") (pin "2") (pinfunction "2_2") (pintype "passive"))
      (node (ref "R67") (pin "2") (pinfunction "2_2") (pintype "passive"))
      (node (ref "R69") (pin "2") (pinfunction "2_2") (pintype "passive"))
      (node (ref "R7") (pin "2") (pinfunction "2_2") (pintype "passive"))
      (node (ref "R77") (pin "2") (pinfunction "2_2") (pintype "passive"))
      (node (ref "R79") (pin "2") (pinfunction "2_2") (pintype "passive"))
      (node (ref "R81") (pin "2") (pinfunction "2_2") (pintype "passive"))
      (node (ref "R89") (pin "2") (pinfunction "2_2") (pintype "passive"))
      (node (ref "R9") (pin "2") (pinfunction "2_2") (pintype "passive"))
      (node (ref "R91") (pin "2") (pinfunction "2_2") (pintype "passive"))
      (node (ref "R93") (pin "2") (pinfunction "2_2") (pintype "passive"))
    )
    (net (code "147") (name "5V0_INT") (class "Default")
      (node (ref "J_EXTRA") (pin "1") (pinfunction "1_1") (pintype "passive"))
    )
    (net (code "148") (name "12V0_PWIN") (class "Default")
      (node (ref "INPUT") (pin "1") (pinfunction "1_1") (pintype "passive"))
      (node (ref "INPUT2") (pin "1") (pinfunction "1_1") (pintype "passive"))
    )
    (net (code "149") (name "GND") (class "Default")
      (node (ref "INPUT") (pin "4") (pinfunction "4_4") (pintype "passive"))
      (node (ref "INPUT2") (pin "4") (pinfunction "4_4") (pintype "passive"))
      (node (ref "J1") (pin "2") (pinfunction "2_2") (pintype "passive"))
      (node (ref "J10") (pin "2") (pinfunction "2_2") (pintype "passive"))
      (node (ref "J11") (pin "2") (pinfunction "2_2") (pintype "passive"))
      (node (ref "J12") (pin "2") (pinfunction "2_2") (pintype "passive"))
      (node (ref "J13") (pin "2") (pinfunction "2_2") (pintype "passive"))
      (node (ref "J14") (pin "2") (pinfunction "2_2") (pintype "passive"))
      (node (ref "J15") (pin "2") (pinfunction "2_2") (pintype "passive"))
      (node (ref "J16") (pin "2") (pinfunction "2_2") (pintype "passive"))
      (node (ref "J17") (pin "2") (pinfunction "2_2") (pintype "passive"))
      (node (ref "J18") (pin "2") (pinfunction "2_2") (pintype "passive"))
      (node (ref "J19") (pin "2") (pinfunction "2_2") (pintype "passive"))
      (node (ref "J2") (pin "2") (pinfunction "2_2") (pintype "passive"))
      (node (ref "J20") (pin "2") (pinfunction "2_2") (pintype "passive"))
      (node (ref "J21") (pin "2") (pinfunction "2_2") (pintype "passive"))
      (node (ref "J22") (pin "2") (pinfunction "2_2") (pintype "passive"))
      (node (ref "J23") (pin "2") (pinfunction "2_2") (pintype "passive"))
      (node (ref "J24") (pin "2") (pinfunction "2_2") (pintype "passive"))
      (node (ref "J25") (pin "2") (pinfunction "2_2") (pintype "passive"))
      (node (ref "J26") (pin "2") (pinfunction "2_2") (pintype "passive"))
      (node (ref "J27") (pin "2") (pinfunction "2_2") (pintype "passive"))
      (node (ref "J3") (pin "2") (pinfunction "2_2") (pintype "passive"))
      (node (ref "J4") (pin "2") (pinfunction "2_2") (pintype "passive"))
      (node (ref "J5") (pin "2") (pinfunction "2_2") (pintype "passive"))
      (node (ref "J6") (pin "2") (pinfunction "2_2") (pintype "passive"))
      (node (ref "J7") (pin "2") (pinfunction "2_2") (pintype "passive"))
      (node (ref "J8") (pin "2") (pinfunction "2_2") (pintype "passive"))
      (node (ref "J9") (pin "2") (pinfunction "2_2") (pintype "passive"))
      (node (ref "J_BOS") (pin "5") (pinfunction "5_5") (pintype "passive"))
      (node (ref "J_EXTRA") (pin "5") (pinfunction "5_5") (pintype "passive"))
    )
    (net (code "150") (name "Net-(J1-Pad4)") (class "Default")
      (node (ref "J1") (pin "4") (pinfunction "4_4") (pintype "passive"))
      (node (ref "R1") (pin "1") (pinfunction "1_1") (pintype "passive"))
    )
    (net (code "151") (name "Net-(J1-Pad6)") (class "Default")
      (node (ref "J1") (pin "6") (pinfunction "6_6") (pintype "passive"))
      (node (ref "R4") (pin "1") (pinfunction "1_1") (pintype "passive"))
    )
    (net (code "152") (name "Net-(J2-Pad4)") (class "Default")
      (node (ref "J2") (pin "4") (pinfunction "4_4") (pintype "passive"))
      (node (ref "R2") (pin "1") (pinfunction "1_1") (pintype "passive"))
    )
    (net (code "153") (name "Net-(J2-Pad6)") (class "Default")
      (node (ref "J2") (pin "6") (pinfunction "6_6") (pintype "passive"))
      (node (ref "R6") (pin "1") (pinfunction "1_1") (pintype "passive"))
    )
    (net (code "154") (name "Net-(J3-Pad4)") (class "Default")
      (node (ref "J3") (pin "4") (pinfunction "4_4") (pintype "passive"))
      (node (ref "R3") (pin "1") (pinfunction "1_1") (pintype "passive"))
    )
    (net (code "155") (name "Net-(J3-Pad6)") (class "Default")
      (node (ref "J3") (pin "6") (pinfunction "6_6") (pintype "passive"))
      (node (ref "R8") (pin "1") (pinfunction "1_1") (pintype "passive"))
    )
    (net (code "156") (name "Net-(J4-Pad4)") (class "Default")
      (node (ref "J4") (pin "4") (pinfunction "4_4") (pintype "passive"))
      (node (ref "R13") (pin "1") (pinfunction "1_1") (pintype "passive"))
    )
    (net (code "157") (name "Net-(J4-Pad6)") (class "Default")
      (node (ref "J4") (pin "6") (pinfunction "6_6") (pintype "passive"))
      (node (ref "R16") (pin "1") (pinfunction "1_1") (pintype "passive"))
    )
    (net (code "158") (name "Net-(J5-Pad4)") (class "Default")
      (node (ref "J5") (pin "4") (pinfunction "4_4") (pintype "passive"))
      (node (ref "R14") (pin "1") (pinfunction "1_1") (pintype "passive"))
    )
    (net (code "159") (name "Net-(J5-Pad6)") (class "Default")
      (node (ref "J5") (pin "6") (pinfunction "6_6") (pintype "passive"))
      (node (ref "R18") (pin "1") (pinfunction "1_1") (pintype "passive"))
    )
    (net (code "160") (name "Net-(J6-Pad4)") (class "Default")
      (node (ref "J6") (pin "4") (pinfunction "4_4") (pintype "passive"))
      (node (ref "R15") (pin "1") (pinfunction "1_1") (pintype "passive"))
    )
    (net (code "161") (name "Net-(J6-Pad6)") (class "Default")
      (node (ref "J6") (pin "6") (pinfunction "6_6") (pintype "passive"))
      (node (ref "R20") (pin "1") (pinfunction "1_1") (pintype "passive"))
    )
    (net (code "162") (name "Net-(J7-Pad4)") (class "Default")
      (node (ref "J7") (pin "4") (pinfunction "4_4") (pintype "passive"))
      (node (ref "R25") (pin "1") (pinfunction "1_1") (pintype "passive"))
    )
    (net (code "163") (name "Net-(J7-Pad6)") (class "Default")
      (node (ref "J7") (pin "6") (pinfunction "6_6") (pintype "passive"))
      (node (ref "R28") (pin "1") (pinfunction "1_1") (pintype "passive"))
    )
    (net (code "164") (name "Net-(J8-Pad4)") (class "Default")
      (node (ref "J8") (pin "4") (pinfunction "4_4") (pintype "passive"))
      (node (ref "R26") (pin "1") (pinfunction "1_1") (pintype "passive"))
    )
    (net (code "165") (name "Net-(J8-Pad6)") (class "Default")
      (node (ref "J8") (pin "6") (pinfunction "6_6") (pintype "passive"))
      (node (ref "R30") (pin "1") (pinfunction "1_1") (pintype "passive"))
    )
    (net (code "166") (name "Net-(J9-Pad4)") (class "Default")
      (node (ref "J9") (pin "4") (pinfunction "4_4") (pintype "passive"))
      (node (ref "R27") (pin "1") (pinfunction "1_1") (pintype "passive"))
    )
    (net (code "167") (name "Net-(J9-Pad6)") (class "Default")
      (node (ref "J9") (pin "6") (pinfunction "6_6") (pintype "passive"))
      (node (ref "R32") (pin "1") (pinfunction "1_1") (pintype "passive"))
    )
    (net (code "168") (name "Net-(J10-Pad4)") (class "Default")
      (node (ref "J10") (pin "4") (pinfunction "4_4") (pintype "passive"))
      (node (ref "R37") (pin "1") (pinfunction "1_1") (pintype "passive"))
    )
    (net (code "169") (name "Net-(J10-Pad6)") (class "Default")
      (node (ref "J10") (pin "6") (pinfunction "6_6") (pintype "passive"))
      (node (ref "R40") (pin "1") (pinfunction "1_1") (pintype "passive"))
    )
    (net (code "170") (name "Net-(J11-Pad4)") (class "Default")
      (node (ref "J11") (pin "4") (pinfunction "4_4") (pintype "passive"))
      (node (ref "R38") (pin "1") (pinfunction "1_1") (pintype "passive"))
    )
    (net (code "171") (name "Net-(J11-Pad6)") (class "Default")
      (node (ref "J11") (pin "6") (pinfunction "6_6") (pintype "passive"))
      (node (ref "R42") (pin "1") (pinfunction "1_1") (pintype "passive"))
    )
    (net (code "172") (name "Net-(J12-Pad4)") (class "Default")
      (node (ref "J12") (pin "4") (pinfunction "4_4") (pintype "passive"))
      (node (ref "R39") (pin "1") (pinfunction "1_1") (pintype "passive"))
    )
    (net (code "173") (name "Net-(J12-Pad6)") (class "Default")
      (node (ref "J12") (pin "6") (pinfunction "6_6") (pintype "passive"))
      (node (ref "R44") (pin "1") (pinfunction "1_1") (pintype "passive"))
    )
    (net (code "174") (name "Net-(J13-Pad4)") (class "Default")
      (node (ref "J13") (pin "4") (pinfunction "4_4") (pintype "passive"))
      (node (ref "R49") (pin "1") (pinfunction "1_1") (pintype "passive"))
    )
    (net (code "175") (name "Net-(J13-Pad6)") (class "Default")
      (node (ref "J13") (pin "6") (pinfunction "6_6") (pintype "passive"))
      (node (ref "R52") (pin "1") (pinfunction "1_1") (pintype "passive"))
    )
    (net (code "176") (name "Net-(J14-Pad4)") (class "Default")
      (node (ref "J14") (pin "4") (pinfunction "4_4") (pintype "passive"))
      (node (ref "R50") (pin "1") (pinfunction "1_1") (pintype "passive"))
    )
    (net (code "177") (name "Net-(J14-Pad6)") (class "Default")
      (node (ref "J14") (pin "6") (pinfunction "6_6") (pintype "passive"))
      (node (ref "R54") (pin "1") (pinfunction "1_1") (pintype "passive"))
    )
    (net (code "178") (name "Net-(J15-Pad4)") (class "Default")
      (node (ref "J15") (pin "4") (pinfunction "4_4") (pintype "passive"))
      (node (ref "R51") (pin "1") (pinfunction "1_1") (pintype "passive"))
    )
    (net (code "179") (name "Net-(J15-Pad6)") (class "Default")
      (node (ref "J15") (pin "6") (pinfunction "6_6") (pintype "passive"))
      (node (ref "R56") (pin "1") (pinfunction "1_1") (pintype "passive"))
    )
    (net (code "180") (name "Net-(J16-Pad4)") (class "Default")
      (node (ref "J16") (pin "4") (pinfunction "4_4") (pintype "passive"))
      (node (ref "R61") (pin "1") (pinfunction "1_1") (pintype "passive"))
    )
    (net (code "181") (name "Net-(J16-Pad6)") (class "Default")
      (node (ref "J16") (pin "6") (pinfunction "6_6") (pintype "passive"))
      (node (ref "R64") (pin "1") (pinfunction "1_1") (pintype "passive"))
    )
    (net (code "182") (name "Net-(J17-Pad4)") (class "Default")
      (node (ref "J17") (pin "4") (pinfunction "4_4") (pintype "passive"))
      (node (ref "R62") (pin "1") (pinfunction "1_1") (pintype "passive"))
    )
    (net (code "183") (name "Net-(J17-Pad6)") (class "Default")
      (node (ref "J17") (pin "6") (pinfunction "6_6") (pintype "passive"))
      (node (ref "R66") (pin "1") (pinfunction "1_1") (pintype "passive"))
    )
    (net (code "184") (name "Net-(J18-Pad4)") (class "Default")
      (node (ref "J18") (pin "4") (pinfunction "4_4") (pintype "passive"))
      (node (ref "R63") (pin "1") (pinfunction "1_1") (pintype "passive"))
    )
    (net (code "185") (name "Net-(J18-Pad6)") (class "Default")
      (node (ref "J18") (pin "6") (pinfunction "6_6") (pintype "passive"))
      (node (ref "R68") (pin "1") (pinfunction "1_1") (pintype "passive"))
    )
    (net (code "186") (name "Net-(J19-Pad4)") (class "Default")
      (node (ref "J19") (pin "4") (pinfunction "4_4") (pintype "passive"))
      (node (ref "R73") (pin "1") (pinfunction "1_1") (pintype "passive"))
    )
    (net (code "187") (name "Net-(J19-Pad6)") (class "Default")
      (node (ref "J19") (pin "6") (pinfunction "6_6") (pintype "passive"))
      (node (ref "R76") (pin "1") (pinfunction "1_1") (pintype "passive"))
    )
    (net (code "188") (name "Net-(J20-Pad4)") (class "Default")
      (node (ref "J20") (pin "4") (pinfunction "4_4") (pintype "passive"))
      (node (ref "R74") (pin "1") (pinfunction "1_1") (pintype "passive"))
    )
    (net (code "189") (name "Net-(J20-Pad6)") (class "Default")
      (node (ref "J20") (pin "6") (pinfunction "6_6") (pintype "passive"))
      (node (ref "R78") (pin "1") (pinfunction "1_1") (pintype "passive"))
    )
    (net (code "190") (name "Net-(J21-Pad4)") (class "Default")
      (node (ref "J21") (pin "4") (pinfunction "4_4") (pintype "passive"))
      (node (ref "R75") (pin "1") (pinfunction "1_1") (pintype "passive"))
    )
    (net (code "191") (name "Net-(J21-Pad6)") (class "Default")
      (node (ref "J21") (pin "6") (pinfunction "6_6") (pintype "passive"))
      (node (ref "R80") (pin "1") (pinfunction "1_1") (pintype "passive"))
    )
    (net (code "192") (name "Net-(J22-Pad4)") (class "Default")
      (node (ref "J22") (pin "4") (pinfunction "4_4") (pintype "passive"))
      (node (ref "R85") (pin "1") (pinfunction "1_1") (pintype "passive"))
    )
    (net (code "193") (name "Net-(J22-Pad6)") (class "Default")
      (node (ref "J22") (pin "6") (pinfunction "6_6") (pintype "passive"))
      (node (ref "R88") (pin "1") (pinfunction "1_1") (pintype "passive"))
    )
    (net (code "194") (name "Net-(J23-Pad4)") (class "Default")
      (node (ref "J23") (pin "4") (pinfunction "4_4") (pintype "passive"))
      (node (ref "R86") (pin "1") (pinfunction "1_1") (pintype "passive"))
    )
    (net (code "195") (name "Net-(J23-Pad6)") (class "Default")
      (node (ref "J23") (pin "6") (pinfunction "6_6") (pintype "passive"))
      (node (ref "R90") (pin "1") (pinfunction "1_1") (pintype "passive"))
    )
    (net (code "196") (name "Net-(J24-Pad4)") (class "Default")
      (node (ref "J24") (pin "4") (pinfunction "4_4") (pintype "passive"))
      (node (ref "R87") (pin "1") (pinfunction "1_1") (pintype "passive"))
    )
    (net (code "197") (name "Net-(J24-Pad6)") (class "Default")
      (node (ref "J24") (pin "6") (pinfunction "6_6") (pintype "passive"))
      (node (ref "R92") (pin "1") (pinfunction "1_1") (pintype "passive"))
    )
    (net (code "198") (name "Net-(J25-Pad4)") (class "Default")
      (node (ref "J25") (pin "4") (pinfunction "4_4") (pintype "passive"))
      (node (ref "R97") (pin "1") (pinfunction "1_1") (pintype "passive"))
    )
    (net (code "199") (name "Net-(J25-Pad6)") (class "Default")
      (node (ref "J25") (pin "6") (pinfunction "6_6") (pintype "passive"))
      (node (ref "R100") (pin "1") (pinfunction "1_1") (pintype "passive"))
    )
    (net (code "200") (name "Net-(J26-Pad4)") (class "Default")
      (node (ref "J26") (pin "4") (pinfunction "4_4") (pintype "passive"))
      (node (ref "R98") (pin "1") (pinfunction "1_1") (pintype "passive"))
    )
    (net (code "201") (name "Net-(J26-Pad6)") (class "Default")
      (node (ref "J26") (pin "6") (pinfunction "6_6") (pintype "passive"))
      (node (ref "R102") (pin "1") (pinfunction "1_1") (pintype "passive"))
    )
    (net (code "202") (name "Net-(J27-Pad4)") (class "Default")
      (node (ref "J27") (pin "4") (pinfunction "4_4") (pintype "passive"))
      (node (ref "R99") (pin "1") (pinfunction "1_1") (pintype "passive"))
    )
    (net (code "203") (name "Net-(J27-Pad6)") (class "Default")
      (node (ref "J27") (pin "6") (pinfunction "6_6") (pintype "passive"))
      (node (ref "R104") (pin "1") (pinfunction "1_1") (pintype "passive"))
    )
    (net (code "204") (name "Net-(Q1-D)") (class "Default")
      (node (ref "J3") (pin "1") (pinfunction "1_1") (pintype "passive"))
      (node (ref "Q1") (pin "3") (pinfunction "D_3") (pintype "passive"))
    )
    (net (code "205") (name "Net-(Q1-G)") (class "Default")
      (node (ref "Q1") (pin "1") (pinfunction "G_1") (pintype "passive"))
      (node (ref "R12") (pin "1") (pinfunction "1_1") (pintype "passive"))
      (node (ref "R9") (pin "1") (pinfunction "1_1") (pintype "passive"))
    )
    (net (code "206") (name "Net-(Q2-D)") (class "Default")
      (node (ref "J1") (pin "1") (pinfunction "1_1") (pintype "passive"))
      (node (ref "Q2") (pin "3") (pinfunction "D_3") (pintype "passive"))
    )
    (net (code "207") (name "Net-(Q2-G)") (class "Default")
      (node (ref "Q2") (pin "1") (pinfunction "G_1") (pintype "passive"))
      (node (ref "R10") (pin "1") (pinfunction "1_1") (pintype "passive"))
      (node (ref "R5") (pin "1") (pinfunction "1_1") (pintype "passive"))
    )
    (net (code "208") (name "Net-(Q3-D)") (class "Default")
      (node (ref "J2") (pin "1") (pinfunction "1_1") (pintype "passive"))
      (node (ref "Q3") (pin "3") (pinfunction "D_3") (pintype "passive"))
    )
    (net (code "209") (name "Net-(Q3-G)") (class "Default")
      (node (ref "Q3") (pin "1") (pinfunction "G_1") (pintype "passive"))
      (node (ref "R11") (pin "1") (pinfunction "1_1") (pintype "passive"))
      (node (ref "R7") (pin "1") (pinfunction "1_1") (pintype "passive"))
    )
    (net (code "210") (name "Net-(Q4-D)") (class "Default")
      (node (ref "J6") (pin "1") (pinfunction "1_1") (pintype "passive"))
      (node (ref "Q4") (pin "3") (pinfunction "D_3") (pintype "passive"))
    )
    (net (code "211") (name "Net-(Q4-G)") (class "Default")
      (node (ref "Q4") (pin "1") (pinfunction "G_1") (pintype "passive"))
      (node (ref "R21") (pin "1") (pinfunction "1_1") (pintype "passive"))
      (node (ref "R24") (pin "1") (pinfunction "1_1") (pintype "passive"))
    )
    (net (code "212") (name "Net-(Q5-D)") (class "Default")
      (node (ref "J4") (pin "1") (pinfunction "1_1") (pintype "passive"))
      (node (ref "Q5") (pin "3") (pinfunction "D_3") (pintype "passive"))
    )
    (net (code "213") (name "Net-(Q5-G)") (class "Default")
      (node (ref "Q5") (pin "1") (pinfunction "G_1") (pintype "passive"))
      (node (ref "R17") (pin "1") (pinfunction "1_1") (pintype "passive"))
      (node (ref "R22") (pin "1") (pinfunction "1_1") (pintype "passive"))
    )
    (net (code "214") (name "Net-(Q6-D)") (class "Default")
      (node (ref "J5") (pin "1") (pinfunction "1_1") (pintype "passive"))
      (node (ref "Q6") (pin "3") (pinfunction "D_3") (pintype "passive"))
    )
    (net (code "215") (name "Net-(Q6-G)") (class "Default")
      (node (ref "Q6") (pin "1") (pinfunction "G_1") (pintype "passive"))
      (node (ref "R19") (pin "1") (pinfunction "1_1") (pintype "passive"))
      (node (ref "R23") (pin "1") (pinfunction "1_1") (pintype "passive"))
    )
    (net (code "216") (name "Net-(Q7-D)") (class "Default")
      (node (ref "J7") (pin "1") (pinfunction "1_1") (pintype "passive"))
      (node (ref "Q7") (pin "3") (pinfunction "D_3") (pintype "passive"))
    )
    (net (code "217") (name "Net-(Q7-G)") (class "Default")
      (node (ref "Q7") (pin "1") (pinfunction "G_1") (pintype "passive"))
      (node (ref "R29") (pin "1") (pinfunction "1_1") (pintype "passive"))
      (node (ref "R34") (pin "1") (pinfunction "1_1") (pintype "passive"))
    )
    (net (code "218") (name "Net-(Q8-D)") (class "Default")
      (node (ref "J8") (pin "1") (pinfunction "1_1") (pintype "passive"))
      (node (ref "Q8") (pin "3") (pinfunction "D_3") (pintype "passive"))
    )
    (net (code "219") (name "Net-(Q8-G)") (class "Default")
      (node (ref "Q8") (pin "1") (pinfunction "G_1") (pintype "passive"))
      (node (ref "R31") (pin "1") (pinfunction "1_1") (pintype "passive"))
      (node (ref "R35") (pin "1") (pinfunction "1_1") (pintype "passive"))
    )
    (net (code "220") (name "Net-(Q9-D)") (class "Default")
      (node (ref "J9") (pin "1") (pinfunction "1_1") (pintype "passive"))
      (node (ref "Q9") (pin "3") (pinfunction "D_3") (pintype "passive"))
    )
    (net (code "221") (name "Net-(Q9-G)") (class "Default")
      (node (ref "Q9") (pin "1") (pinfunction "G_1") (pintype "passive"))
      (node (ref "R33") (pin "1") (pinfunction "1_1") (pintype "passive"))
      (node (ref "R36") (pin "1") (pinfunction "1_1") (pintype "passive"))
    )
    (net (code "222") (name "Net-(Q10-D)") (class "Default")
      (node (ref "J10") (pin "1") (pinfunction "1_1") (pintype "passive"))
      (node (ref "Q10") (pin "3") (pinfunction "D_3") (pintype "passive"))
    )
    (net (code "223") (name "Net-(Q10-G)") (class "Default")
      (node (ref "Q10") (pin "1") (pinfunction "G_1") (pintype "passive"))
      (node (ref "R41") (pin "1") (pinfunction "1_1") (pintype "passive"))
      (node (ref "R46") (pin "1") (pinfunction "1_1") (pintype "passive"))
    )
    (net (code "224") (name "Net-(Q11-D)") (class "Default")
      (node (ref "J12") (pin "1") (pinfunction "1_1") (pintype "passive"))
      (node (ref "Q11") (pin "3") (pinfunction "D_3") (pintype "passive"))
    )
    (net (code "225") (name "Net-(Q11-G)") (class "Default")
      (node (ref "Q11") (pin "1") (pinfunction "G_1") (pintype "passive"))
      (node (ref "R45") (pin "1") (pinfunction "1_1") (pintype "passive"))
      (node (ref "R48") (pin "1") (pinfunction "1_1") (pintype "passive"))
    )
    (net (code "226") (name "Net-(Q12-D)") (class "Default")
      (node (ref "J11") (pin "1") (pinfunction "1_1") (pintype "passive"))
      (node (ref "Q12") (pin "3") (pinfunction "D_3") (pintype "passive"))
    )
    (net (code "227") (name "Net-(Q12-G)") (class "Default")
      (node (ref "Q12") (pin "1") (pinfunction "G_1") (pintype "passive"))
      (node (ref "R43") (pin "1") (pinfunction "1_1") (pintype "passive"))
      (node (ref "R47") (pin "1") (pinfunction "1_1") (pintype "passive"))
    )
    (net (code "228") (name "Net-(Q13-D)") (class "Default")
      (node (ref "J15") (pin "1") (pinfunction "1_1") (pintype "passive"))
      (node (ref "Q13") (pin "3") (pinfunction "D_3") (pintype "passive"))
    )
    (net (code "229") (name "Net-(Q13-G)") (class "Default")
      (node (ref "Q13") (pin "1") (pinfunction "G_1") (pintype "passive"))
      (node (ref "R57") (pin "1") (pinfunction "1_1") (pintype "passive"))
      (node (ref "R60") (pin "1") (pinfunction "1_1") (pintype "passive"))
    )
    (net (code "230") (name "Net-(Q14-D)") (class "Default")
      (node (ref "J14") (pin "1") (pinfunction "1_1") (pintype "passive"))
      (node (ref "Q14") (pin "3") (pinfunction "D_3") (pintype "passive"))
    )
    (net (code "231") (name "Net-(Q14-G)") (class "Default")
      (node (ref "Q14") (pin "1") (pinfunction "G_1") (pintype "passive"))
      (node (ref "R55") (pin "1") (pinfunction "1_1") (pintype "passive"))
      (node (ref "R59") (pin "1") (pinfunction "1_1") (pintype "passive"))
    )
    (net (code "232") (name "Net-(Q15-D)") (class "Default")
      (node (ref "J13") (pin "1") (pinfunction "1_1") (pintype "passive"))
      (node (ref "Q15") (pin "3") (pinfunction "D_3") (pintype "passive"))
    )
    (net (code "233") (name "Net-(Q15-G)") (class "Default")
      (node (ref "Q15") (pin "1") (pinfunction "G_1") (pintype "passive"))
      (node (ref "R53") (pin "1") (pinfunction "1_1") (pintype "passive"))
      (node (ref "R58") (pin "1") (pinfunction "1_1") (pintype "passive"))
    )
    (net (code "234") (name "Net-(Q16-D)") (class "Default")
      (node (ref "J16") (pin "1") (pinfunction "1_1") (pintype "passive"))
      (node (ref "Q16") (pin "3") (pinfunction "D_3") (pintype "passive"))
    )
    (net (code "235") (name "Net-(Q16-G)") (class "Default")
      (node (ref "Q16") (pin "1") (pinfunction "G_1") (pintype "passive"))
      (node (ref "R65") (pin "1") (pinfunction "1_1") (pintype "passive"))
      (node (ref "R70") (pin "1") (pinfunction "1_1") (pintype "passive"))
    )
    (net (code "236") (name "Net-(Q17-D)") (class "Default")
      (node (ref "J17") (pin "1") (pinfunction "1_1") (pintype "passive"))
      (node (ref "Q17") (pin "3") (pinfunction "D_3") (pintype "passive"))
    )
    (net (code "237") (name "Net-(Q17-G)") (class "Default")
      (node (ref "Q17") (pin "1") (pinfunction "G_1") (pintype "passive"))
      (node (ref "R67") (pin "1") (pinfunction "1_1") (pintype "passive"))
      (node (ref "R71") (pin "1") (pinfunction "1_1") (pintype "passive"))
    )
    (net (code "238") (name "Net-(Q18-D)") (class "Default")
      (node (ref "J18") (pin "1") (pinfunction "1_1") (pintype "passive"))
      (node (ref "Q18") (pin "3") (pinfunction "D_3") (pintype "passive"))
    )
    (net (code "239") (name "Net-(Q18-G)") (class "Default")
      (node (ref "Q18") (pin "1") (pinfunction "G_1") (pintype "passive"))
      (node (ref "R69") (pin "1") (pinfunction "1_1") (pintype "passive"))
      (node (ref "R72") (pin "1") (pinfunction "1_1") (pintype "passive"))
    )
    (net (code "240") (name "Net-(Q19-D)") (class "Default")
      (node (ref "J19") (pin "1") (pinfunction "1_1") (pintype "passive"))
      (node (ref "Q19") (pin "3") (pinfunction "D_3") (pintype "passive"))
    )
    (net (code "241") (name "Net-(Q19-G)") (class "Default")
      (node (ref "Q19") (pin "1") (pinfunction "G_1") (pintype "passive"))
      (node (ref "R77") (pin "1") (pinfunction "1_1") (pintype "passive"))
      (node (ref "R82") (pin "1") (pinfunction "1_1") (pintype "passive"))
    )
    (net (code "242") (name "Net-(Q20-D)") (class "Default")
      (node (ref "J20") (pin "1") (pinfunction "1_1") (pintype "passive"))
      (node (ref "Q20") (pin "3") (pinfunction "D_3") (pintype "passive"))
    )
    (net (code "243") (name "Net-(Q20-G)") (class "Default")
      (node (ref "Q20") (pin "1") (pinfunction "G_1") (pintype "passive"))
      (node (ref "R79") (pin "1") (pinfunction "1_1") (pintype "passive"))
      (node (ref "R83") (pin "1") (pinfunction "1_1") (pintype "passive"))
    )
    (net (code "244") (name "Net-(Q21-D)") (class "Default")
      (node (ref "J21") (pin "1") (pinfunction "1_1") (pintype "passive"))
      (node (ref "Q21") (pin "3") (pinfunction "D_3") (pintype "passive"))
    )
    (net (code "245") (name "Net-(Q21-G)") (class "Default")
      (node (ref "Q21") (pin "1") (pinfunction "G_1") (pintype "passive"))
      (node (ref "R81") (pin "1") (pinfunction "1_1") (pintype "passive"))
      (node (ref "R84") (pin "1") (pinfunction "1_1") (pintype "passive"))
    )
    (net (code "246") (name "Net-(Q22-D)") (class "Default")
      (node (ref "J22") (pin "1") (pinfunction "1_1") (pintype "passive"))
      (node (ref "Q22") (pin "3") (pinfunction "D_3") (pintype "passive"))
    )
    (net (code "247") (name "Net-(Q22-G)") (class "Default")
      (node (ref "Q22") (pin "1") (pinfunction "G_1") (pintype "passive"))
      (node (ref "R89") (pin "1") (pinfunction "1_1") (pintype "passive"))
      (node (ref "R94") (pin "1") (pinfunction "1_1") (pintype "passive"))
    )
    (net (code "248") (name "Net-(Q23-D)") (class "Default")
      (node (ref "J23") (pin "1") (pinfunction "1_1") (pintype "passive"))
      (node (ref "Q23") (pin "3") (pinfunction "D_3") (pintype "passive"))
    )
    (net (code "249") (name "Net-(Q23-G)") (class "Default")
      (node (ref "Q23") (pin "1") (pinfunction "G_1") (pintype "passive"))
      (node (ref "R91") (pin "1") (pinfunction "1_1") (pintype "passive"))
      (node (ref "R95") (pin "1") (pinfunction "1_1") (pintype "passive"))
    )
    (net (code "250") (name "Net-(Q24-D)") (class "Default")
      (node (ref "J24") (pin "1") (pinfunction "1_1") (pintype "passive"))
      (node (ref "Q24") (pin "3") (pinfunction "D_3") (pintype "passive"))
    )
    (net (code "251") (name "Net-(Q24-G)") (class "Default")
      (node (ref "Q24") (pin "1") (pinfunction "G_1") (pintype "passive"))
      (node (ref "R93") (pin "1") (pinfunction "1_1") (pintype "passive"))
      (node (ref "R96") (pin "1") (pinfunction "1_1") (pintype "passive"))
    )
    (net (code "252") (name "Net-(Q25-D)") (class "Default")
      (node (ref "J25") (pin "1") (pinfunction "1_1") (pintype "passive"))
      (node (ref "Q25") (pin "3") (pinfunction "D_3") (pintype "passive"))
    )
    (net (code "253") (name "Net-(Q25-G)") (class "Default")
      (node (ref "Q25") (pin "1") (pinfunction "G_1") (pintype "passive"))
      (node (ref "R101") (pin "1") (pinfunction "1_1") (pintype "passive"))
      (node (ref "R106") (pin "1") (pinfunction "1_1") (pintype "passive"))
    )
    (net (code "254") (name "Net-(Q26-D)") (class "Default")
      (node (ref "J27") (pin "1") (pinfunction "1_1") (pintype "passive"))
      (node (ref "Q26") (pin "3") (pinfunction "D_3") (pintype "passive"))
    )
    (net (code "255") (name "Net-(Q26-G)") (class "Default")
      (node (ref "Q26") (pin "1") (pinfunction "G_1") (pintype "passive"))
      (node (ref "R105") (pin "1") (pinfunction "1_1") (pintype "passive"))
      (node (ref "R108") (pin "1") (pinfunction "1_1") (pintype "passive"))
    )
    (net (code "256") (name "Net-(Q27-D)") (class "Default")
      (node (ref "J26") (pin "1") (pinfunction "1_1") (pintype "passive"))
      (node (ref "Q27") (pin "3") (pinfunction "D_3") (pintype "passive"))
    )
    (net (code "257") (name "Net-(Q27-G)") (class "Default")
      (node (ref "Q27") (pin "1") (pinfunction "G_1") (pintype "passive"))
      (node (ref "R103") (pin "1") (pinfunction "1_1") (pintype "passive"))
      (node (ref "R107") (pin "1") (pinfunction "1_1") (pintype "passive"))
    )
    (net (code "258") (name "VDD_MCU") (class "Default")
      (node (ref "J_BOS") (pin "1") (pinfunction "1_1") (pintype "passive"))
    )
    (net (code "259") (name "unconnected-(J_BOS-Pad6)") (class "Default")
      (node (ref "J_BOS") (pin "6") (pinfunction "6_6") (pintype "passive"))
    )
  )
)
